# Replicape_A4.net
KiCad netlist of a schematic drawn in EAGLE
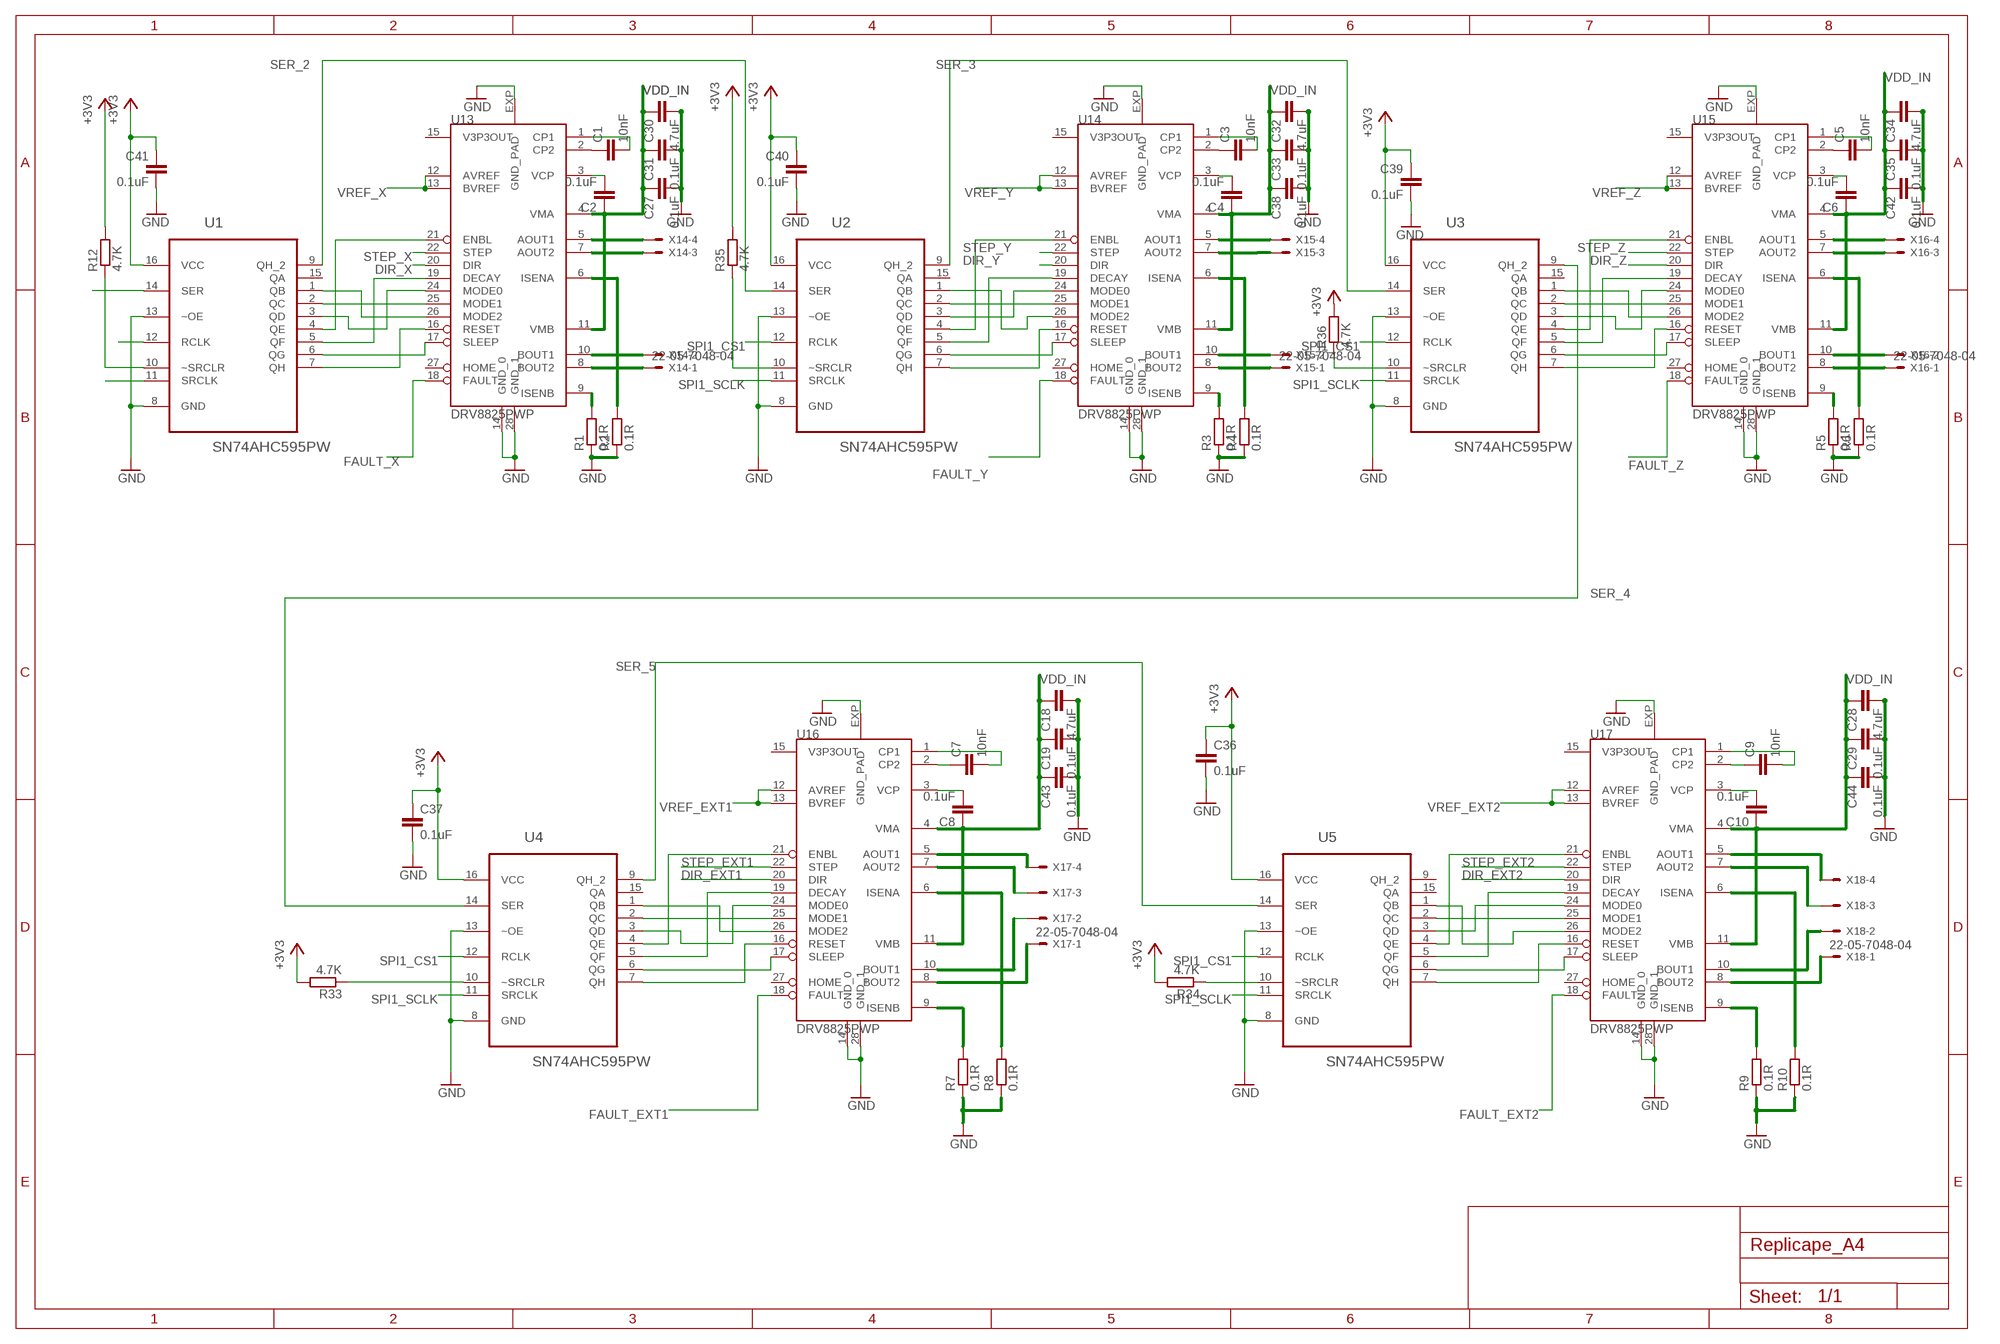
[diagram p0: schematic, sheet 1, part 1 of 3]
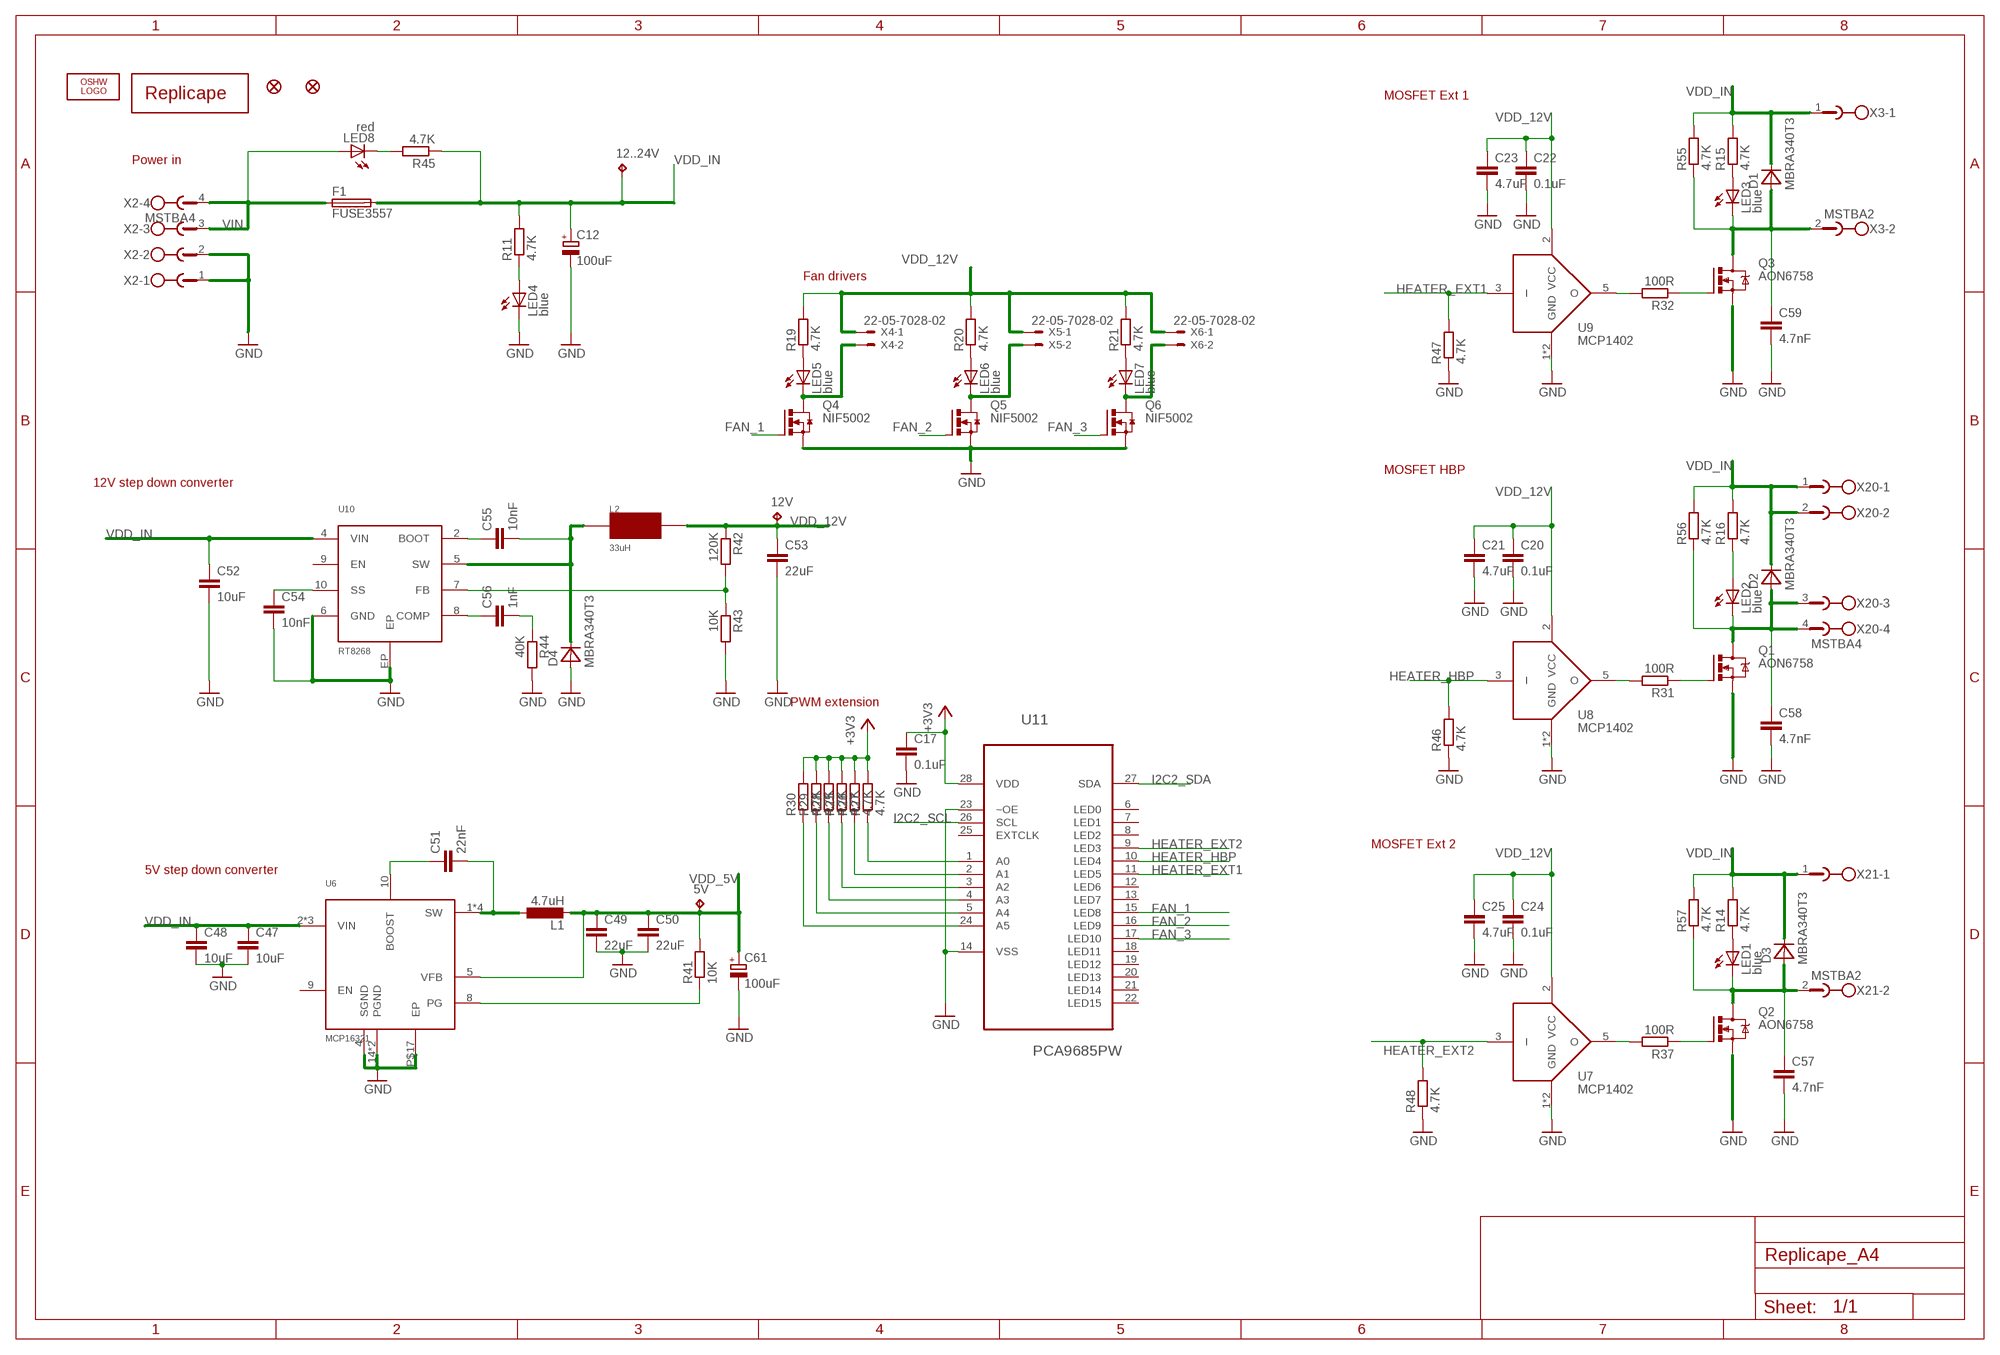
[diagram p1: schematic, sheet 1, part 2 of 3]
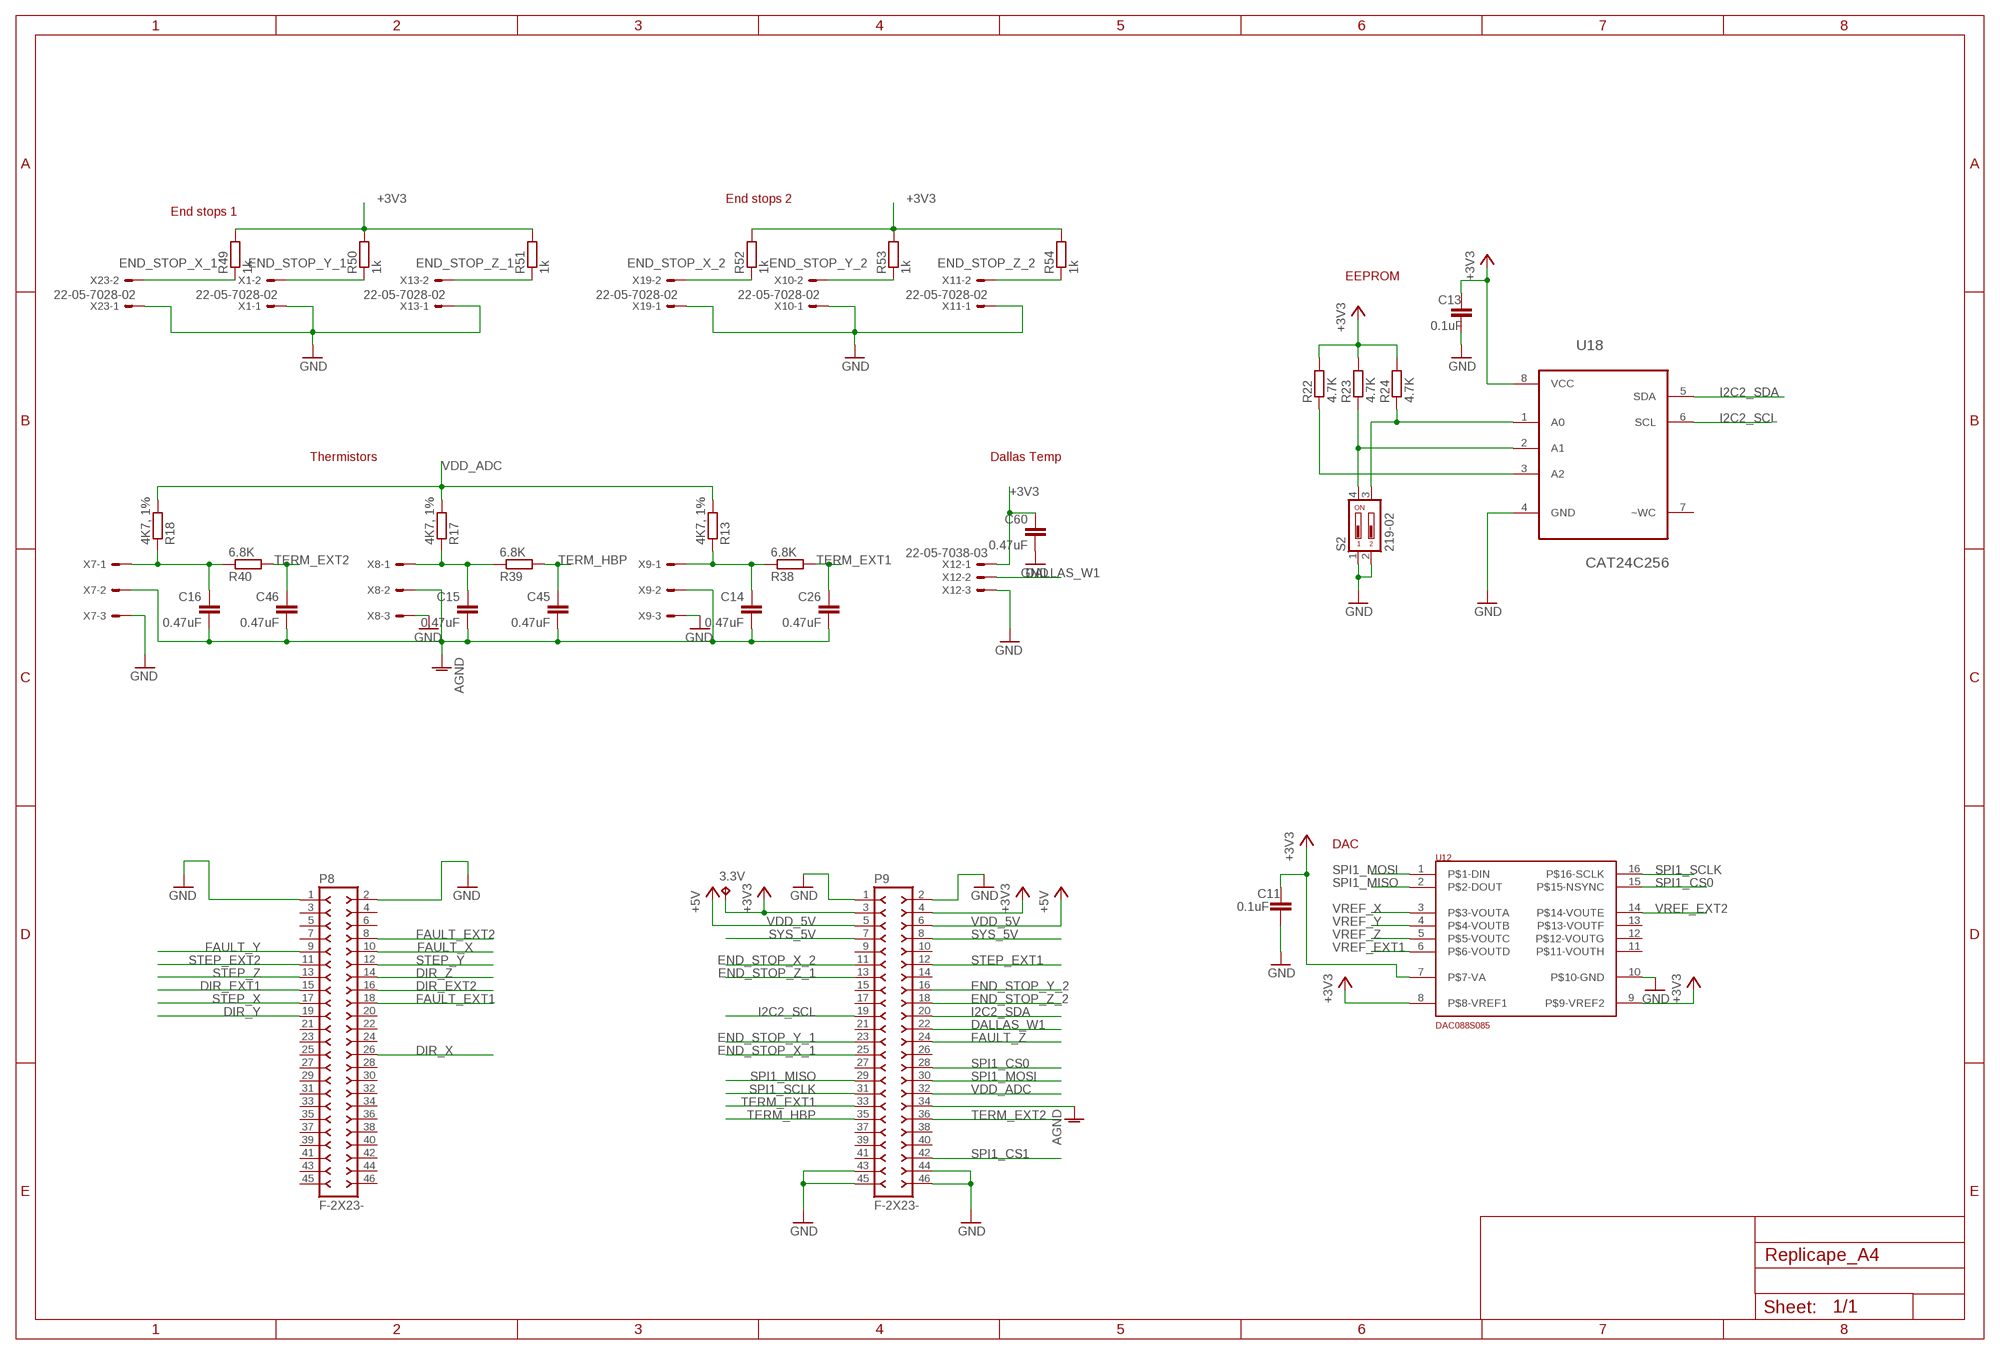
[diagram p2: schematic, sheet 1, part 3 of 3]

(export (version "E")
  (design (tool "Eeschema 10.0.6"))
  (components
    (comp (ref "3.3V")
      (value "TPB1,27")
      (footprint "eagle-import:B1,27")
      (libsource (lib "eagle-import") (part "TPB1,27"))
    )
    (comp (ref "5V")
      (value "TPB1,27")
      (footprint "eagle-import:B1,27")
      (libsource (lib "eagle-import") (part "TPB1,27"))
    )
    (comp (ref "12..24V")
      (value "TPB1,27")
      (footprint "eagle-import:B1,27")
      (libsource (lib "eagle-import") (part "TPB1,27"))
    )
    (comp (ref "12V")
      (value "TPB1,27")
      (footprint "eagle-import:B1,27")
      (libsource (lib "eagle-import") (part "TPB1,27"))
    )
    (comp (ref "C1")
      (value "10nF")
      (footprint "eagle-import:C0402")
      (libsource (lib "eagle-import") (part "C-EUC0402"))
    )
    (comp (ref "C2")
      (value "0.1uF")
      (footprint "eagle-import:C0402")
      (libsource (lib "eagle-import") (part "C-EUC0402"))
    )
    (comp (ref "C3")
      (value "10nF")
      (footprint "eagle-import:C0402")
      (libsource (lib "eagle-import") (part "C-EUC0402"))
    )
    (comp (ref "C4")
      (value "0.1uF")
      (footprint "eagle-import:C0402")
      (libsource (lib "eagle-import") (part "C-EUC0402"))
    )
    (comp (ref "C5")
      (value "10nF")
      (footprint "eagle-import:C0402")
      (libsource (lib "eagle-import") (part "C-EUC0402"))
    )
    (comp (ref "C6")
      (value "0.1uF")
      (footprint "eagle-import:C0402")
      (libsource (lib "eagle-import") (part "C-EUC0402"))
    )
    (comp (ref "C7")
      (value "10nF")
      (footprint "eagle-import:C0402")
      (libsource (lib "eagle-import") (part "C-EUC0402"))
    )
    (comp (ref "C8")
      (value "0.1uF")
      (footprint "eagle-import:C0402")
      (libsource (lib "eagle-import") (part "C-EUC0402"))
    )
    (comp (ref "C9")
      (value "10nF")
      (footprint "eagle-import:C0402")
      (libsource (lib "eagle-import") (part "C-EUC0402"))
    )
    (comp (ref "C10")
      (value "0.1uF")
      (footprint "eagle-import:C0402")
      (libsource (lib "eagle-import") (part "C-EUC0402"))
    )
    (comp (ref "C11")
      (value "0.1uF")
      (footprint "eagle-import:C0402")
      (libsource (lib "eagle-import") (part "C-EUC0402"))
    )
    (comp (ref "C12")
      (value "100uF")
      (footprint "eagle-import:140CLH-0810")
      (libsource (lib "eagle-import") (part "CPOL-EU140CLH-0810"))
    )
    (comp (ref "C13")
      (value "0.1uF")
      (footprint "eagle-import:C0402")
      (libsource (lib "eagle-import") (part "C-EUC0402"))
    )
    (comp (ref "C14")
      (value "0.47uF")
      (footprint "eagle-import:C0402")
      (libsource (lib "eagle-import") (part "C-EUC0402"))
    )
    (comp (ref "C15")
      (value "0.47uF")
      (footprint "eagle-import:C0402")
      (libsource (lib "eagle-import") (part "C-EUC0402"))
    )
    (comp (ref "C16")
      (value "0.47uF")
      (footprint "eagle-import:C0402")
      (libsource (lib "eagle-import") (part "C-EUC0402"))
    )
    (comp (ref "C17")
      (value "0.1uF")
      (footprint "eagle-import:C0402")
      (libsource (lib "eagle-import") (part "C-EUC0402"))
    )
    (comp (ref "C18")
      (value "4.7uF")
      (footprint "eagle-import:C0603")
      (libsource (lib "eagle-import") (part "C-EUC0603"))
    )
    (comp (ref "C19")
      (value "0.1uF")
      (footprint "eagle-import:C0402")
      (libsource (lib "eagle-import") (part "C-EUC0402"))
    )
    (comp (ref "C20")
      (value "0.1uF")
      (footprint "eagle-import:C0402")
      (libsource (lib "eagle-import") (part "C-EUC0402"))
    )
    (comp (ref "C21")
      (value "4.7uF")
      (footprint "eagle-import:C0402")
      (libsource (lib "eagle-import") (part "C-EUC0402"))
    )
    (comp (ref "C22")
      (value "0.1uF")
      (footprint "eagle-import:C0402")
      (libsource (lib "eagle-import") (part "C-EUC0402"))
    )
    (comp (ref "C23")
      (value "4.7uF")
      (footprint "eagle-import:C0402")
      (libsource (lib "eagle-import") (part "C-EUC0402"))
    )
    (comp (ref "C24")
      (value "0.1uF")
      (footprint "eagle-import:C0402")
      (libsource (lib "eagle-import") (part "C-EUC0402"))
    )
    (comp (ref "C25")
      (value "4.7uF")
      (footprint "eagle-import:C0402")
      (libsource (lib "eagle-import") (part "C-EUC0402"))
    )
    (comp (ref "C26")
      (value "0.47uF")
      (footprint "eagle-import:C0402")
      (libsource (lib "eagle-import") (part "C-EUC0402"))
    )
    (comp (ref "C27")
      (value "0.1uF")
      (footprint "eagle-import:C0402")
      (libsource (lib "eagle-import") (part "C-EUC0402"))
    )
    (comp (ref "C28")
      (value "4.7uF")
      (footprint "eagle-import:C0603")
      (libsource (lib "eagle-import") (part "C-EUC0603"))
    )
    (comp (ref "C29")
      (value "0.1uF")
      (footprint "eagle-import:C0402")
      (libsource (lib "eagle-import") (part "C-EUC0402"))
    )
    (comp (ref "C30")
      (value "4.7uF")
      (footprint "eagle-import:C0603")
      (libsource (lib "eagle-import") (part "C-EUC0603"))
    )
    (comp (ref "C31")
      (value "0.1uF")
      (footprint "eagle-import:C0402")
      (libsource (lib "eagle-import") (part "C-EUC0402"))
    )
    (comp (ref "C32")
      (value "4.7uF")
      (footprint "eagle-import:C0603")
      (libsource (lib "eagle-import") (part "C-EUC0603"))
    )
    (comp (ref "C33")
      (value "0.1uF")
      (footprint "eagle-import:C0402")
      (libsource (lib "eagle-import") (part "C-EUC0402"))
    )
    (comp (ref "C34")
      (value "4.7uF")
      (footprint "eagle-import:C0603")
      (libsource (lib "eagle-import") (part "C-EUC0603"))
    )
    (comp (ref "C35")
      (value "0.1uF")
      (footprint "eagle-import:C0402")
      (libsource (lib "eagle-import") (part "C-EUC0402"))
    )
    (comp (ref "C36")
      (value "0.1uF")
      (footprint "eagle-import:C0402")
      (libsource (lib "eagle-import") (part "C-EUC0402"))
    )
    (comp (ref "C37")
      (value "0.1uF")
      (footprint "eagle-import:C0402")
      (libsource (lib "eagle-import") (part "C-EUC0402"))
    )
    (comp (ref "C38")
      (value "0.1uF")
      (footprint "eagle-import:C0402")
      (libsource (lib "eagle-import") (part "C-EUC0402"))
    )
    (comp (ref "C39")
      (value "0.1uF")
      (footprint "eagle-import:C0402")
      (libsource (lib "eagle-import") (part "C-EUC0402"))
    )
    (comp (ref "C40")
      (value "0.1uF")
      (footprint "eagle-import:C0402")
      (libsource (lib "eagle-import") (part "C-EUC0402"))
    )
    (comp (ref "C41")
      (value "0.1uF")
      (footprint "eagle-import:C0402")
      (libsource (lib "eagle-import") (part "C-EUC0402"))
    )
    (comp (ref "C42")
      (value "0.1uF")
      (footprint "eagle-import:C0402")
      (libsource (lib "eagle-import") (part "C-EUC0402"))
    )
    (comp (ref "C43")
      (value "0.1uF")
      (footprint "eagle-import:C0402")
      (libsource (lib "eagle-import") (part "C-EUC0402"))
    )
    (comp (ref "C44")
      (value "0.1uF")
      (footprint "eagle-import:C0402")
      (libsource (lib "eagle-import") (part "C-EUC0402"))
    )
    (comp (ref "C45")
      (value "0.47uF")
      (footprint "eagle-import:C0402")
      (libsource (lib "eagle-import") (part "C-EUC0402"))
    )
    (comp (ref "C46")
      (value "0.47uF")
      (footprint "eagle-import:C0402")
      (libsource (lib "eagle-import") (part "C-EUC0402"))
    )
    (comp (ref "C47")
      (value "10uF")
      (footprint "eagle-import:C1206")
      (libsource (lib "eagle-import") (part "C-EUC1206"))
    )
    (comp (ref "C48")
      (value "10uF")
      (footprint "eagle-import:C1206")
      (libsource (lib "eagle-import") (part "C-EUC1206"))
    )
    (comp (ref "C49")
      (value "22uF")
      (footprint "eagle-import:C0805")
      (libsource (lib "eagle-import") (part "C-EUC0805"))
    )
    (comp (ref "C50")
      (value "22uF")
      (footprint "eagle-import:C0805")
      (libsource (lib "eagle-import") (part "C-EUC0805"))
    )
    (comp (ref "C51")
      (value "22nF")
      (footprint "eagle-import:C0402")
      (libsource (lib "eagle-import") (part "C-EUC0402"))
    )
    (comp (ref "C52")
      (value "10uF")
      (footprint "eagle-import:C1206")
      (libsource (lib "eagle-import") (part "C-EUC1206"))
    )
    (comp (ref "C53")
      (value "22uF")
      (footprint "eagle-import:C0805")
      (libsource (lib "eagle-import") (part "C-EUC0805"))
    )
    (comp (ref "C54")
      (value "10nF")
      (footprint "eagle-import:C0402")
      (libsource (lib "eagle-import") (part "C-EUC0402"))
    )
    (comp (ref "C55")
      (value "10nF")
      (footprint "eagle-import:C0402")
      (libsource (lib "eagle-import") (part "C-EUC0402"))
    )
    (comp (ref "C56")
      (value "1nF")
      (footprint "eagle-import:C0402")
      (libsource (lib "eagle-import") (part "C-EUC0402"))
    )
    (comp (ref "C57")
      (value "4.7nF")
      (footprint "eagle-import:C0402")
      (libsource (lib "eagle-import") (part "C-EUC0402"))
    )
    (comp (ref "C58")
      (value "4.7nF")
      (footprint "eagle-import:C0402")
      (libsource (lib "eagle-import") (part "C-EUC0402"))
    )
    (comp (ref "C59")
      (value "4.7nF")
      (footprint "eagle-import:C0402")
      (libsource (lib "eagle-import") (part "C-EUC0402"))
    )
    (comp (ref "C60")
      (value "0.47uF")
      (footprint "eagle-import:C0402")
      (libsource (lib "eagle-import") (part "C-EUC0402"))
    )
    (comp (ref "C61")
      (value "100uF")
      (footprint "eagle-import:140CLH-0810")
      (libsource (lib "eagle-import") (part "CPOL-EU140CLH-0810"))
    )
    (comp (ref "D1")
      (value "MBRA340T3")
      (footprint "eagle-import:SMA")
      (libsource (lib "eagle-import") (part "MBRA340T3"))
    )
    (comp (ref "D2")
      (value "MBRA340T3")
      (footprint "eagle-import:SMA")
      (libsource (lib "eagle-import") (part "MBRA340T3"))
    )
    (comp (ref "D3")
      (value "MBRA340T3")
      (footprint "eagle-import:SMA")
      (libsource (lib "eagle-import") (part "MBRA340T3"))
    )
    (comp (ref "D4")
      (value "MBRA340T3")
      (footprint "eagle-import:SMA")
      (libsource (lib "eagle-import") (part "MBRA340T3"))
    )
    (comp (ref "F1")
      (value "FUSE3557")
      (footprint "eagle-import:3557")
      (libsource (lib "eagle-import") (part "FUSE3557"))
    )
    (comp (ref "JP1")
      (value "FIDUCIAL1X2.5")
      (footprint "eagle-import:FIDUCIAL-1X2.5")
      (libsource (lib "eagle-import") (part "FIDUCIAL1X2.5"))
    )
    (comp (ref "JP2")
      (value "FIDUCIAL1X2.5")
      (footprint "eagle-import:FIDUCIAL-1X2.5")
      (libsource (lib "eagle-import") (part "FIDUCIAL1X2.5"))
    )
    (comp (ref "L1")
      (value "4.7uH")
      (footprint "eagle-import:VLC5020")
      (libsource (lib "eagle-import") (part "L-EUVLC"))
    )
    (comp (ref "L2")
      (value "33uH")
      (footprint "eagle-import:NR8040T330")
      (libsource (lib "eagle-import") (part "RT8040T330"))
    )
    (comp (ref "LED1")
      (value "blue")
      (footprint "eagle-import:CHIP-LED0603")
      (libsource (lib "eagle-import") (part "LEDCHIP-LED0603"))
    )
    (comp (ref "LED2")
      (value "blue")
      (footprint "eagle-import:CHIP-LED0603")
      (libsource (lib "eagle-import") (part "LEDCHIP-LED0603"))
    )
    (comp (ref "LED3")
      (value "blue")
      (footprint "eagle-import:CHIP-LED0603")
      (libsource (lib "eagle-import") (part "LEDCHIP-LED0603"))
    )
    (comp (ref "LED4")
      (value "blue")
      (footprint "eagle-import:CHIP-LED0603")
      (libsource (lib "eagle-import") (part "LEDCHIP-LED0603"))
    )
    (comp (ref "LED5")
      (value "blue")
      (footprint "eagle-import:CHIP-LED0603")
      (libsource (lib "eagle-import") (part "LEDCHIP-LED0603"))
    )
    (comp (ref "LED6")
      (value "blue")
      (footprint "eagle-import:CHIP-LED0603")
      (libsource (lib "eagle-import") (part "LEDCHIP-LED0603"))
    )
    (comp (ref "LED7")
      (value "blue")
      (footprint "eagle-import:CHIP-LED0603")
      (libsource (lib "eagle-import") (part "LEDCHIP-LED0603"))
    )
    (comp (ref "LED8")
      (value "red")
      (footprint "eagle-import:CHIP-LED0603")
      (libsource (lib "eagle-import") (part "LEDCHIP-LED0603"))
    )
    (comp (ref "LOGO1")
      (value "OSHW_LOGO_FILLX0200-NT")
      (footprint "eagle-import:OSHW_FILLX200_NOTEXT")
      (libsource (lib "eagle-import") (part "OSHW_LOGO_FILLX0200-NT"))
    )
    (comp (ref "P8")
      (value "F-2X23-")
      (footprint "eagle-import:DIL-100-2X23")
      (libsource (lib "eagle-import") (part "F-2X23-"))
    )
    (comp (ref "P9")
      (value "F-2X23-")
      (footprint "eagle-import:DIL-100-2X23")
      (libsource (lib "eagle-import") (part "F-2X23-"))
    )
    (comp (ref "Q1")
      (value "AON6758")
      (footprint "eagle-import:8-DFN-EP-(5X6)")
      (libsource (lib "eagle-import") (part "AON6758"))
    )
    (comp (ref "Q2")
      (value "AON6758")
      (footprint "eagle-import:8-DFN-EP-(5X6)")
      (libsource (lib "eagle-import") (part "AON6758"))
    )
    (comp (ref "Q3")
      (value "AON6758")
      (footprint "eagle-import:8-DFN-EP-(5X6)")
      (libsource (lib "eagle-import") (part "AON6758"))
    )
    (comp (ref "Q4")
      (value "NIF5002")
      (footprint "eagle-import:SOT223")
      (libsource (lib "eagle-import") (part "N-HEXFET-2D_?-SOT232"))
    )
    (comp (ref "Q5")
      (value "NIF5002")
      (footprint "eagle-import:SOT223")
      (libsource (lib "eagle-import") (part "N-HEXFET-2D_?-SOT232"))
    )
    (comp (ref "Q6")
      (value "NIF5002")
      (footprint "eagle-import:SOT223")
      (libsource (lib "eagle-import") (part "N-HEXFET-2D_?-SOT232"))
    )
    (comp (ref "R1")
      (value "0.1R")
      (footprint "eagle-import:R0805")
      (libsource (lib "eagle-import") (part "R-EU_R0805"))
    )
    (comp (ref "R2")
      (value "0.1R")
      (footprint "eagle-import:R0805")
      (libsource (lib "eagle-import") (part "R-EU_R0805"))
    )
    (comp (ref "R3")
      (value "0.1R")
      (footprint "eagle-import:R0805")
      (libsource (lib "eagle-import") (part "R-EU_R0805"))
    )
    (comp (ref "R4")
      (value "0.1R")
      (footprint "eagle-import:R0805")
      (libsource (lib "eagle-import") (part "R-EU_R0805"))
    )
    (comp (ref "R5")
      (value "0.1R")
      (footprint "eagle-import:R0805")
      (libsource (lib "eagle-import") (part "R-EU_R0805"))
    )
    (comp (ref "R6")
      (value "0.1R")
      (footprint "eagle-import:R0805")
      (libsource (lib "eagle-import") (part "R-EU_R0805"))
    )
    (comp (ref "R7")
      (value "0.1R")
      (footprint "eagle-import:R0805")
      (libsource (lib "eagle-import") (part "R-EU_R0805"))
    )
    (comp (ref "R8")
      (value "0.1R")
      (footprint "eagle-import:R0805")
      (libsource (lib "eagle-import") (part "R-EU_R0805"))
    )
    (comp (ref "R9")
      (value "0.1R")
      (footprint "eagle-import:R0805")
      (libsource (lib "eagle-import") (part "R-EU_R0805"))
    )
    (comp (ref "R10")
      (value "0.1R")
      (footprint "eagle-import:R0805")
      (libsource (lib "eagle-import") (part "R-EU_R0805"))
    )
    (comp (ref "R11")
      (value "4.7K")
      (footprint "eagle-import:R0402")
      (libsource (lib "eagle-import") (part "R-EU_R0402"))
    )
    (comp (ref "R12")
      (value "4.7K")
      (footprint "eagle-import:R0402")
      (libsource (lib "eagle-import") (part "R-EU_R0402"))
    )
    (comp (ref "R13")
      (value "4K7, 1%")
      (footprint "eagle-import:R0402")
      (libsource (lib "eagle-import") (part "R-EU_R0402"))
    )
    (comp (ref "R14")
      (value "4.7K")
      (footprint "eagle-import:R0402")
      (libsource (lib "eagle-import") (part "R-EU_R0402"))
    )
    (comp (ref "R15")
      (value "4.7K")
      (footprint "eagle-import:R0402")
      (libsource (lib "eagle-import") (part "R-EU_R0402"))
    )
    (comp (ref "R16")
      (value "4.7K")
      (footprint "eagle-import:R0402")
      (libsource (lib "eagle-import") (part "R-EU_R0402"))
    )
    (comp (ref "R17")
      (value "4K7, 1%")
      (footprint "eagle-import:R0402")
      (libsource (lib "eagle-import") (part "R-EU_R0402"))
    )
    (comp (ref "R18")
      (value "4K7, 1%")
      (footprint "eagle-import:R0402")
      (libsource (lib "eagle-import") (part "R-EU_R0402"))
    )
    (comp (ref "R19")
      (value "4.7K")
      (footprint "eagle-import:R0402")
      (libsource (lib "eagle-import") (part "R-EU_R0402"))
    )
    (comp (ref "R20")
      (value "4.7K")
      (footprint "eagle-import:R0402")
      (libsource (lib "eagle-import") (part "R-EU_R0402"))
    )
    (comp (ref "R21")
      (value "4.7K")
      (footprint "eagle-import:R0402")
      (libsource (lib "eagle-import") (part "R-EU_R0402"))
    )
    (comp (ref "R22")
      (value "4.7K")
      (footprint "eagle-import:R0402")
      (libsource (lib "eagle-import") (part "R-EU_R0402"))
    )
    (comp (ref "R23")
      (value "4.7K")
      (footprint "eagle-import:R0402")
      (libsource (lib "eagle-import") (part "R-EU_R0402"))
    )
    (comp (ref "R24")
      (value "4.7K")
      (footprint "eagle-import:R0402")
      (libsource (lib "eagle-import") (part "R-EU_R0402"))
    )
    (comp (ref "R25")
      (value "4.7K")
      (footprint "eagle-import:R0402")
      (libsource (lib "eagle-import") (part "R-EU_R0402"))
    )
    (comp (ref "R26")
      (value "4.7K")
      (footprint "eagle-import:R0402")
      (libsource (lib "eagle-import") (part "R-EU_R0402"))
    )
    (comp (ref "R27")
      (value "4.7K")
      (footprint "eagle-import:R0402")
      (libsource (lib "eagle-import") (part "R-EU_R0402"))
    )
    (comp (ref "R28")
      (value "4.7K")
      (footprint "eagle-import:R0402")
      (libsource (lib "eagle-import") (part "R-EU_R0402"))
    )
    (comp (ref "R29")
      (value "4.7K")
      (footprint "eagle-import:R0402")
      (libsource (lib "eagle-import") (part "R-EU_R0402"))
    )
    (comp (ref "R30")
      (value "4.7K")
      (footprint "eagle-import:R0402")
      (libsource (lib "eagle-import") (part "R-EU_R0402"))
    )
    (comp (ref "R31")
      (value "100R")
      (footprint "eagle-import:R0402")
      (libsource (lib "eagle-import") (part "R-EU_R0402"))
    )
    (comp (ref "R32")
      (value "100R")
      (footprint "eagle-import:R0402")
      (libsource (lib "eagle-import") (part "R-EU_R0402"))
    )
    (comp (ref "R33")
      (value "4.7K")
      (footprint "eagle-import:R0402")
      (libsource (lib "eagle-import") (part "R-EU_R0402"))
    )
    (comp (ref "R34")
      (value "4.7K")
      (footprint "eagle-import:R0402")
      (libsource (lib "eagle-import") (part "R-EU_R0402"))
    )
    (comp (ref "R35")
      (value "4.7K")
      (footprint "eagle-import:R0402")
      (libsource (lib "eagle-import") (part "R-EU_R0402"))
    )
    (comp (ref "R36")
      (value "4.7K")
      (footprint "eagle-import:R0402")
      (libsource (lib "eagle-import") (part "R-EU_R0402"))
    )
    (comp (ref "R37")
      (value "100R")
      (footprint "eagle-import:R0402")
      (libsource (lib "eagle-import") (part "R-EU_R0402"))
    )
    (comp (ref "R38")
      (value "6.8K")
      (footprint "eagle-import:R0402")
      (libsource (lib "eagle-import") (part "R-EU_R0402"))
    )
    (comp (ref "R39")
      (value "6.8K")
      (footprint "eagle-import:R0402")
      (libsource (lib "eagle-import") (part "R-EU_R0402"))
    )
    (comp (ref "R40")
      (value "6.8K")
      (footprint "eagle-import:R0402")
      (libsource (lib "eagle-import") (part "R-EU_R0402"))
    )
    (comp (ref "R41")
      (value "10K")
      (footprint "eagle-import:R0402")
      (libsource (lib "eagle-import") (part "R-EU_R0402"))
    )
    (comp (ref "R42")
      (value "120K")
      (footprint "eagle-import:R0402")
      (libsource (lib "eagle-import") (part "R-EU_R0402"))
    )
    (comp (ref "R43")
      (value "10K")
      (footprint "eagle-import:R0402")
      (libsource (lib "eagle-import") (part "R-EU_R0402"))
    )
    (comp (ref "R44")
      (value "40K")
      (footprint "eagle-import:R0402")
      (libsource (lib "eagle-import") (part "R-EU_R0402"))
    )
    (comp (ref "R45")
      (value "4.7K")
      (footprint "eagle-import:R0402")
      (libsource (lib "eagle-import") (part "R-EU_R0402"))
    )
    (comp (ref "R46")
      (value "4.7K")
      (footprint "eagle-import:R0402")
      (libsource (lib "eagle-import") (part "R-EU_R0402"))
    )
    (comp (ref "R47")
      (value "4.7K")
      (footprint "eagle-import:R0402")
      (libsource (lib "eagle-import") (part "R-EU_R0402"))
    )
    (comp (ref "R48")
      (value "4.7K")
      (footprint "eagle-import:R0402")
      (libsource (lib "eagle-import") (part "R-EU_R0402"))
    )
    (comp (ref "R49")
      (value "1k")
      (footprint "eagle-import:R0402")
      (libsource (lib "eagle-import") (part "R-EUR0402"))
    )
    (comp (ref "R50")
      (value "1k")
      (footprint "eagle-import:R0402")
      (libsource (lib "eagle-import") (part "R-EUR0402"))
    )
    (comp (ref "R51")
      (value "1k")
      (footprint "eagle-import:R0402")
      (libsource (lib "eagle-import") (part "R-EUR0402"))
    )
    (comp (ref "R52")
      (value "1k")
      (footprint "eagle-import:R0402")
      (libsource (lib "eagle-import") (part "R-EUR0402"))
    )
    (comp (ref "R53")
      (value "1k")
      (footprint "eagle-import:R0402")
      (libsource (lib "eagle-import") (part "R-EUR0402"))
    )
    (comp (ref "R54")
      (value "1k")
      (footprint "eagle-import:R0402")
      (libsource (lib "eagle-import") (part "R-EUR0402"))
    )
    (comp (ref "R55")
      (value "4.7K")
      (footprint "eagle-import:R0402")
      (libsource (lib "eagle-import") (part "R-EU_R0402"))
    )
    (comp (ref "R56")
      (value "4.7K")
      (footprint "eagle-import:R0402")
      (libsource (lib "eagle-import") (part "R-EU_R0402"))
    )
    (comp (ref "R57")
      (value "4.7K")
      (footprint "eagle-import:R0402")
      (libsource (lib "eagle-import") (part "R-EU_R0402"))
    )
    (comp (ref "S2")
      (value "219-02")
      (footprint "eagle-import:CTS-219-02")
      (libsource (lib "eagle-import") (part "219-02"))
    )
    (comp (ref "U$2")
      (value "REPLICAPE-LOGO")
      (footprint "eagle-import:REPLICAPE-LOGO")
      (libsource (lib "eagle-import") (part "REPLICAPE-LOGO"))
    )
    (comp (ref "U1")
      (value "SN74AHC595PW")
      (footprint "eagle-import:SOP65P640X120-16N")
      (libsource (lib "eagle-import") (part "SN74AHC595PW"))
    )
    (comp (ref "U2")
      (value "SN74AHC595PW")
      (footprint "eagle-import:SOP65P640X120-16N")
      (libsource (lib "eagle-import") (part "SN74AHC595PW"))
    )
    (comp (ref "U3")
      (value "SN74AHC595PW")
      (footprint "eagle-import:SOP65P640X120-16N")
      (libsource (lib "eagle-import") (part "SN74AHC595PW"))
    )
    (comp (ref "U4")
      (value "SN74AHC595PW")
      (footprint "eagle-import:SOP65P640X120-16N")
      (libsource (lib "eagle-import") (part "SN74AHC595PW"))
    )
    (comp (ref "U5")
      (value "SN74AHC595PW")
      (footprint "eagle-import:SOP65P640X120-16N")
      (libsource (lib "eagle-import") (part "SN74AHC595PW"))
    )
    (comp (ref "U6")
      (value "MCP16321")
      (footprint "eagle-import:QFN-16")
      (libsource (lib "eagle-import") (part "MCP16321"))
    )
    (comp (ref "U7")
      (value "MCP1402")
      (footprint "eagle-import:SOT23-5L")
      (libsource (lib "eagle-import") (part "MCP1402"))
    )
    (comp (ref "U8")
      (value "MCP1402")
      (footprint "eagle-import:SOT23-5L")
      (libsource (lib "eagle-import") (part "MCP1402"))
    )
    (comp (ref "U9")
      (value "MCP1402")
      (footprint "eagle-import:SOT23-5L")
      (libsource (lib "eagle-import") (part "MCP1402"))
    )
    (comp (ref "U10")
      (value "RT8268")
      (footprint "eagle-import:MSOP10")
      (libsource (lib "eagle-import") (part "RT8268"))
    )
    (comp (ref "U11")
      (value "PCA9685PW")
      (footprint "eagle-import:SOP65P640X110-28N")
      (libsource (lib "eagle-import") (part "PCA9685PW"))
    )
    (comp (ref "U12")
      (value "DAC088S085")
      (footprint "eagle-import:TSSOP-16")
      (libsource (lib "eagle-import") (part "DAC088S085"))
    )
    (comp (ref "U13")
      (value "DRV8825PWP")
      (footprint "eagle-import:TSSOP-28")
      (libsource (lib "eagle-import") (part "DRV8825PWP"))
    )
    (comp (ref "U14")
      (value "DRV8825PWP")
      (footprint "eagle-import:TSSOP-28")
      (libsource (lib "eagle-import") (part "DRV8825PWP"))
    )
    (comp (ref "U15")
      (value "DRV8825PWP")
      (footprint "eagle-import:TSSOP-28")
      (libsource (lib "eagle-import") (part "DRV8825PWP"))
    )
    (comp (ref "U16")
      (value "DRV8825PWP")
      (footprint "eagle-import:TSSOP-28")
      (libsource (lib "eagle-import") (part "DRV8825PWP"))
    )
    (comp (ref "U17")
      (value "DRV8825PWP")
      (footprint "eagle-import:TSSOP-28")
      (libsource (lib "eagle-import") (part "DRV8825PWP"))
    )
    (comp (ref "U18")
      (value "CAT24C256")
      (footprint "eagle-import:SOIC127P600X175-8N")
      (libsource (lib "eagle-import") (part "CAT24C256"))
    )
    (comp (ref "X1")
      (value "22-05-7028-02")
      (footprint "eagle-import:7395-02")
      (libsource (lib "eagle-import") (part "22-?-0205-7028"))
    )
    (comp (ref "X2")
      (value "MSTBA4")
      (footprint "eagle-import:MSTBA4")
      (libsource (lib "eagle-import") (part "MSTBA4"))
    )
    (comp (ref "X3")
      (value "MSTBA2")
      (footprint "eagle-import:MSTBA2")
      (libsource (lib "eagle-import") (part "MSTBA2"))
    )
    (comp (ref "X4")
      (value "22-05-7028-02")
      (footprint "eagle-import:7395-02")
      (libsource (lib "eagle-import") (part "22-?-0205-7028"))
    )
    (comp (ref "X5")
      (value "22-05-7028-02")
      (footprint "eagle-import:7395-02")
      (libsource (lib "eagle-import") (part "22-?-0205-7028"))
    )
    (comp (ref "X6")
      (value "22-05-7028-02")
      (footprint "eagle-import:7395-02")
      (libsource (lib "eagle-import") (part "22-?-0205-7028"))
    )
    (comp (ref "X7")
      (value "22-05-7038-03")
      (footprint "eagle-import:7395-03")
      (libsource (lib "eagle-import") (part "22-?-0305-7038"))
    )
    (comp (ref "X8")
      (value "22-05-7038-03")
      (footprint "eagle-import:7395-03")
      (libsource (lib "eagle-import") (part "22-?-0305-7038"))
    )
    (comp (ref "X9")
      (value "22-05-7038-03")
      (footprint "eagle-import:7395-03")
      (libsource (lib "eagle-import") (part "22-?-0305-7038"))
    )
    (comp (ref "X10")
      (value "22-05-7028-02")
      (footprint "eagle-import:7395-02")
      (libsource (lib "eagle-import") (part "22-?-0205-7028"))
    )
    (comp (ref "X11")
      (value "22-05-7028-02")
      (footprint "eagle-import:7395-02")
      (libsource (lib "eagle-import") (part "22-?-0205-7028"))
    )
    (comp (ref "X12")
      (value "22-05-7038-03")
      (footprint "eagle-import:7395-03")
      (libsource (lib "eagle-import") (part "22-?-0305-7038"))
    )
    (comp (ref "X13")
      (value "22-05-7028-02")
      (footprint "eagle-import:7395-02")
      (libsource (lib "eagle-import") (part "22-?-0205-7028"))
    )
    (comp (ref "X14")
      (value "22-05-7048-04")
      (footprint "eagle-import:7395-04")
      (libsource (lib "eagle-import") (part "22-?-0405-7048"))
    )
    (comp (ref "X15")
      (value "22-05-7048-04")
      (footprint "eagle-import:7395-04")
      (libsource (lib "eagle-import") (part "22-?-0405-7048"))
    )
    (comp (ref "X16")
      (value "22-05-7048-04")
      (footprint "eagle-import:7395-04")
      (libsource (lib "eagle-import") (part "22-?-0405-7048"))
    )
    (comp (ref "X17")
      (value "22-05-7048-04")
      (footprint "eagle-import:7395-04")
      (libsource (lib "eagle-import") (part "22-?-0405-7048"))
    )
    (comp (ref "X18")
      (value "22-05-7048-04")
      (footprint "eagle-import:7395-04")
      (libsource (lib "eagle-import") (part "22-?-0405-7048"))
    )
    (comp (ref "X19")
      (value "22-05-7028-02")
      (footprint "eagle-import:7395-02")
      (libsource (lib "eagle-import") (part "22-?-0205-7028"))
    )
    (comp (ref "X20")
      (value "MSTBA4")
      (footprint "eagle-import:MSTBA4")
      (libsource (lib "eagle-import") (part "MSTBA4"))
    )
    (comp (ref "X21")
      (value "MSTBA2")
      (footprint "eagle-import:MSTBA2")
      (libsource (lib "eagle-import") (part "MSTBA2"))
    )
    (comp (ref "X23")
      (value "22-05-7028-02")
      (footprint "eagle-import:7395-02")
      (libsource (lib "eagle-import") (part "22-?-0205-7028"))
    )
  )
  (nets
    (net (code "1") (name "+3V3") (class "Default")
      (node (ref "3.3V") (pin "TP") (pinfunction "TP_TP") (pintype "input"))
      (node (ref "C11") (pin "1") (pinfunction "1_1") (pintype "passive"))
      (node (ref "C13") (pin "1") (pinfunction "1_1") (pintype "passive"))
      (node (ref "C17") (pin "1") (pinfunction "1_1") (pintype "passive"))
      (node (ref "C36") (pin "1") (pinfunction "1_1") (pintype "passive"))
      (node (ref "C37") (pin "1") (pinfunction "1_1") (pintype "passive"))
      (node (ref "C39") (pin "1") (pinfunction "1_1") (pintype "passive"))
      (node (ref "C40") (pin "1") (pinfunction "1_1") (pintype "passive"))
      (node (ref "C41") (pin "1") (pinfunction "1_1") (pintype "passive"))
      (node (ref "C60") (pin "1") (pinfunction "1_1") (pintype "passive"))
      (node (ref "P9") (pin "3") (pinfunction "3_3") (pintype "passive"))
      (node (ref "P9") (pin "4") (pinfunction "4_4") (pintype "passive"))
      (node (ref "R12") (pin "2") (pinfunction "2_2") (pintype "passive"))
      (node (ref "R22") (pin "2") (pinfunction "2_2") (pintype "passive"))
      (node (ref "R23") (pin "2") (pinfunction "2_2") (pintype "passive"))
      (node (ref "R24") (pin "2") (pinfunction "2_2") (pintype "passive"))
      (node (ref "R25") (pin "2") (pinfunction "2_2") (pintype "passive"))
      (node (ref "R26") (pin "2") (pinfunction "2_2") (pintype "passive"))
      (node (ref "R27") (pin "2") (pinfunction "2_2") (pintype "passive"))
      (node (ref "R28") (pin "2") (pinfunction "2_2") (pintype "passive"))
      (node (ref "R29") (pin "2") (pinfunction "2_2") (pintype "passive"))
      (node (ref "R30") (pin "2") (pinfunction "2_2") (pintype "passive"))
      (node (ref "R33") (pin "2") (pinfunction "2_2") (pintype "passive"))
      (node (ref "R34") (pin "2") (pinfunction "2_2") (pintype "passive"))
      (node (ref "R35") (pin "2") (pinfunction "2_2") (pintype "passive"))
      (node (ref "R36") (pin "2") (pinfunction "2_2") (pintype "passive"))
      (node (ref "R49") (pin "2") (pinfunction "2_2") (pintype "passive"))
      (node (ref "R50") (pin "2") (pinfunction "2_2") (pintype "passive"))
      (node (ref "R51") (pin "2") (pinfunction "2_2") (pintype "passive"))
      (node (ref "R52") (pin "2") (pinfunction "2_2") (pintype "passive"))
      (node (ref "R53") (pin "2") (pinfunction "2_2") (pintype "passive"))
      (node (ref "R54") (pin "2") (pinfunction "2_2") (pintype "passive"))
      (node (ref "U1") (pin "16") (pinfunction "VCC_16") (pintype "power_in"))
      (node (ref "U11") (pin "28") (pinfunction "VDD_28") (pintype "power_in"))
      (node (ref "U12") (pin "7") (pinfunction "P$7-VA_7") (pintype "bidirectional"))
      (node (ref "U12") (pin "8") (pinfunction "P$8-VREF1_8") (pintype "bidirectional"))
      (node (ref "U12") (pin "9") (pinfunction "P$9-VREF2_9") (pintype "bidirectional"))
      (node (ref "U18") (pin "8") (pinfunction "VCC_8") (pintype "power_in"))
      (node (ref "U2") (pin "16") (pinfunction "VCC_16") (pintype "power_in"))
      (node (ref "U3") (pin "16") (pinfunction "VCC_16") (pintype "power_in"))
      (node (ref "U4") (pin "16") (pinfunction "VCC_16") (pintype "power_in"))
      (node (ref "U5") (pin "16") (pinfunction "VCC_16") (pintype "power_in"))
      (node (ref "X12") (pin "1") (pinfunction "S_1") (pintype "passive"))
    )
    (net (code "2") (name "+5V") (class "Default")
      (node (ref "5V") (pin "TP") (pinfunction "TP_TP") (pintype "input"))
      (node (ref "C49") (pin "1") (pinfunction "1_1") (pintype "passive"))
      (node (ref "C50") (pin "1") (pinfunction "1_1") (pintype "passive"))
      (node (ref "C61") (pin "+") (pinfunction "+_+") (pintype "passive"))
      (node (ref "L1") (pin "2") (pinfunction "2_2") (pintype "passive"))
      (node (ref "P9") (pin "5") (pinfunction "5_5") (pintype "passive"))
      (node (ref "P9") (pin "6") (pinfunction "6_6") (pintype "passive"))
      (node (ref "R41") (pin "2") (pinfunction "2_2") (pintype "passive"))
      (node (ref "U6") (pin "5") (pinfunction "VFB_5") (pintype "input"))
    )
    (net (code "3") (name "/DALLAS_W1") (class "Default")
      (node (ref "P9") (pin "22") (pinfunction "22_22") (pintype "passive"))
      (node (ref "X12") (pin "2") (pinfunction "S_2") (pintype "passive"))
    )
    (net (code "4") (name "/DIR_EXT1") (class "Default")
      (node (ref "P8") (pin "15") (pinfunction "15_15") (pintype "passive"))
      (node (ref "U16") (pin "20") (pinfunction "DIR_20") (pintype "input"))
    )
    (net (code "5") (name "/DIR_EXT2") (class "Default")
      (node (ref "P8") (pin "16") (pinfunction "16_16") (pintype "passive"))
      (node (ref "U17") (pin "20") (pinfunction "DIR_20") (pintype "input"))
    )
    (net (code "6") (name "/DIR_X") (class "Default")
      (node (ref "P8") (pin "26") (pinfunction "26_26") (pintype "passive"))
      (node (ref "U13") (pin "20") (pinfunction "DIR_20") (pintype "input"))
    )
    (net (code "7") (name "/DIR_Y") (class "Default")
      (node (ref "P8") (pin "19") (pinfunction "19_19") (pintype "passive"))
      (node (ref "U14") (pin "20") (pinfunction "DIR_20") (pintype "input"))
    )
    (net (code "8") (name "/DIR_Z") (class "Default")
      (node (ref "P8") (pin "14") (pinfunction "14_14") (pintype "passive"))
      (node (ref "U15") (pin "20") (pinfunction "DIR_20") (pintype "input"))
    )
    (net (code "9") (name "/END_STOP_X_1") (class "Default")
      (node (ref "P9") (pin "25") (pinfunction "25_25") (pintype "passive"))
      (node (ref "R49") (pin "1") (pinfunction "1_1") (pintype "passive"))
      (node (ref "X23") (pin "2") (pinfunction "S_2") (pintype "passive"))
    )
    (net (code "10") (name "/END_STOP_X_2") (class "Default")
      (node (ref "P9") (pin "11") (pinfunction "11_11") (pintype "passive"))
      (node (ref "R52") (pin "1") (pinfunction "1_1") (pintype "passive"))
      (node (ref "X19") (pin "2") (pinfunction "S_2") (pintype "passive"))
    )
    (net (code "11") (name "/END_STOP_Y_1") (class "Default")
      (node (ref "P9") (pin "23") (pinfunction "23_23") (pintype "passive"))
      (node (ref "R50") (pin "1") (pinfunction "1_1") (pintype "passive"))
      (node (ref "X1") (pin "2") (pinfunction "S_2") (pintype "passive"))
    )
    (net (code "12") (name "/END_STOP_Y_2") (class "Default")
      (node (ref "P9") (pin "16") (pinfunction "16_16") (pintype "passive"))
      (node (ref "R53") (pin "1") (pinfunction "1_1") (pintype "passive"))
      (node (ref "X10") (pin "2") (pinfunction "S_2") (pintype "passive"))
    )
    (net (code "13") (name "/END_STOP_Z_1") (class "Default")
      (node (ref "P9") (pin "13") (pinfunction "13_13") (pintype "passive"))
      (node (ref "R51") (pin "1") (pinfunction "1_1") (pintype "passive"))
      (node (ref "X13") (pin "2") (pinfunction "S_2") (pintype "passive"))
    )
    (net (code "14") (name "/END_STOP_Z_2") (class "Default")
      (node (ref "P9") (pin "18") (pinfunction "18_18") (pintype "passive"))
      (node (ref "R54") (pin "1") (pinfunction "1_1") (pintype "passive"))
      (node (ref "X11") (pin "2") (pinfunction "S_2") (pintype "passive"))
    )
    (net (code "15") (name "/FAN_1") (class "Default")
      (node (ref "Q4") (pin "1") (pinfunction "G_1") (pintype "passive"))
      (node (ref "U11") (pin "15") (pinfunction "LED8_15") (pintype "output"))
    )
    (net (code "16") (name "/FAN_2") (class "Default")
      (node (ref "Q5") (pin "1") (pinfunction "G_1") (pintype "passive"))
      (node (ref "U11") (pin "16") (pinfunction "LED9_16") (pintype "output"))
    )
    (net (code "17") (name "/FAN_3") (class "Default")
      (node (ref "Q6") (pin "1") (pinfunction "G_1") (pintype "passive"))
      (node (ref "U11") (pin "17") (pinfunction "LED10_17") (pintype "output"))
    )
    (net (code "18") (name "/FAULT_EXT1") (class "Default")
      (node (ref "P8") (pin "18") (pinfunction "18_18") (pintype "passive"))
      (node (ref "U16") (pin "18") (pinfunction "FAULT_18") (pintype "output"))
    )
    (net (code "19") (name "/FAULT_EXT2") (class "Default")
      (node (ref "P8") (pin "8") (pinfunction "8_8") (pintype "passive"))
      (node (ref "U17") (pin "18") (pinfunction "FAULT_18") (pintype "output"))
    )
    (net (code "20") (name "/FAULT_X") (class "Default")
      (node (ref "P8") (pin "10") (pinfunction "10_10") (pintype "passive"))
      (node (ref "U13") (pin "18") (pinfunction "FAULT_18") (pintype "output"))
    )
    (net (code "21") (name "/FAULT_Y") (class "Default")
      (node (ref "P8") (pin "9") (pinfunction "9_9") (pintype "passive"))
      (node (ref "U14") (pin "18") (pinfunction "FAULT_18") (pintype "output"))
    )
    (net (code "22") (name "/FAULT_Z") (class "Default")
      (node (ref "P9") (pin "24") (pinfunction "24_24") (pintype "passive"))
      (node (ref "U15") (pin "18") (pinfunction "FAULT_18") (pintype "output"))
    )
    (net (code "23") (name "/HEATER_EXT1") (class "Default")
      (node (ref "R47") (pin "2") (pinfunction "2_2") (pintype "passive"))
      (node (ref "U11") (pin "11") (pinfunction "LED5_11") (pintype "output"))
      (node (ref "U9") (pin "3") (pinfunction "I_3") (pintype "input"))
    )
    (net (code "24") (name "/HEATER_EXT2") (class "Default")
      (node (ref "R48") (pin "2") (pinfunction "2_2") (pintype "passive"))
      (node (ref "U11") (pin "9") (pinfunction "LED3_9") (pintype "output"))
      (node (ref "U7") (pin "3") (pinfunction "I_3") (pintype "input"))
    )
    (net (code "25") (name "/HEATER_HBP") (class "Default")
      (node (ref "R46") (pin "2") (pinfunction "2_2") (pintype "passive"))
      (node (ref "U11") (pin "10") (pinfunction "LED4_10") (pintype "output"))
      (node (ref "U8") (pin "3") (pinfunction "I_3") (pintype "input"))
    )
    (net (code "26") (name "/I2C2_SCL") (class "Default")
      (node (ref "P9") (pin "19") (pinfunction "19_19") (pintype "passive"))
      (node (ref "U11") (pin "26") (pinfunction "SCL_26") (pintype "input"))
      (node (ref "U18") (pin "6") (pinfunction "SCL_6") (pintype "input"))
    )
    (net (code "27") (name "/I2C2_SDA") (class "Default")
      (node (ref "P9") (pin "20") (pinfunction "20_20") (pintype "passive"))
      (node (ref "U11") (pin "27") (pinfunction "SDA_27") (pintype "bidirectional"))
      (node (ref "U18") (pin "5") (pinfunction "SDA_5") (pintype "bidirectional"))
    )
    (net (code "28") (name "/SER_2") (class "Default")
      (node (ref "U1") (pin "9") (pinfunction "QH_2_9") (pintype "output"))
      (node (ref "U2") (pin "14") (pinfunction "SER_14") (pintype "input"))
    )
    (net (code "29") (name "/SER_3") (class "Default")
      (node (ref "U2") (pin "9") (pinfunction "QH_2_9") (pintype "output"))
      (node (ref "U3") (pin "14") (pinfunction "SER_14") (pintype "input"))
    )
    (net (code "30") (name "/SER_4") (class "Default")
      (node (ref "U3") (pin "9") (pinfunction "QH_2_9") (pintype "output"))
      (node (ref "U4") (pin "14") (pinfunction "SER_14") (pintype "input"))
    )
    (net (code "31") (name "/SER_5") (class "Default")
      (node (ref "U4") (pin "9") (pinfunction "QH_2_9") (pintype "output"))
      (node (ref "U5") (pin "14") (pinfunction "SER_14") (pintype "input"))
    )
    (net (code "32") (name "/SPI1_CS0") (class "Default")
      (node (ref "P9") (pin "28") (pinfunction "28_28") (pintype "passive"))
      (node (ref "U12") (pin "15") (pinfunction "P$15-NSYNC_15") (pintype "bidirectional"))
    )
    (net (code "33") (name "/SPI1_CS1") (class "Default")
      (node (ref "P9") (pin "42") (pinfunction "42_42") (pintype "passive"))
      (node (ref "U1") (pin "12") (pinfunction "RCLK_12") (pintype "input"))
      (node (ref "U2") (pin "12") (pinfunction "RCLK_12") (pintype "input"))
      (node (ref "U3") (pin "12") (pinfunction "RCLK_12") (pintype "input"))
      (node (ref "U4") (pin "12") (pinfunction "RCLK_12") (pintype "input"))
      (node (ref "U5") (pin "12") (pinfunction "RCLK_12") (pintype "input"))
    )
    (net (code "34") (name "/SPI1_MISO") (class "Default")
      (node (ref "P9") (pin "29") (pinfunction "29_29") (pintype "passive"))
      (node (ref "U12") (pin "2") (pinfunction "P$2-DOUT_2") (pintype "bidirectional"))
    )
    (net (code "35") (name "/SPI1_MOSI") (class "Default")
      (node (ref "P9") (pin "30") (pinfunction "30_30") (pintype "passive"))
      (node (ref "U1") (pin "14") (pinfunction "SER_14") (pintype "input"))
      (node (ref "U12") (pin "1") (pinfunction "P$1-DIN_1") (pintype "bidirectional"))
    )
    (net (code "36") (name "/SPI1_SCLK") (class "Default")
      (node (ref "P9") (pin "31") (pinfunction "31_31") (pintype "passive"))
      (node (ref "U1") (pin "11") (pinfunction "SRCLK_11") (pintype "input"))
      (node (ref "U12") (pin "16") (pinfunction "P$16-SCLK_16") (pintype "bidirectional"))
      (node (ref "U2") (pin "11") (pinfunction "SRCLK_11") (pintype "input"))
      (node (ref "U3") (pin "11") (pinfunction "SRCLK_11") (pintype "input"))
      (node (ref "U4") (pin "11") (pinfunction "SRCLK_11") (pintype "input"))
      (node (ref "U5") (pin "11") (pinfunction "SRCLK_11") (pintype "input"))
    )
    (net (code "37") (name "/STEP_EXT1") (class "Default")
      (node (ref "P9") (pin "12") (pinfunction "12_12") (pintype "passive"))
      (node (ref "U16") (pin "22") (pinfunction "STEP_22") (pintype "input"))
    )
    (net (code "38") (name "/STEP_EXT2") (class "Default")
      (node (ref "P8") (pin "11") (pinfunction "11_11") (pintype "passive"))
      (node (ref "U17") (pin "22") (pinfunction "STEP_22") (pintype "input"))
    )
    (net (code "39") (name "/STEP_X") (class "Default")
      (node (ref "P8") (pin "17") (pinfunction "17_17") (pintype "passive"))
      (node (ref "U13") (pin "22") (pinfunction "STEP_22") (pintype "input"))
    )
    (net (code "40") (name "/STEP_Y") (class "Default")
      (node (ref "P8") (pin "12") (pinfunction "12_12") (pintype "passive"))
      (node (ref "U14") (pin "22") (pinfunction "STEP_22") (pintype "input"))
    )
    (net (code "41") (name "/STEP_Z") (class "Default")
      (node (ref "P8") (pin "13") (pinfunction "13_13") (pintype "passive"))
      (node (ref "U15") (pin "22") (pinfunction "STEP_22") (pintype "input"))
    )
    (net (code "42") (name "/SYS_5V") (class "Default")
      (node (ref "P9") (pin "7") (pinfunction "7_7") (pintype "passive"))
      (node (ref "P9") (pin "8") (pinfunction "8_8") (pintype "passive"))
    )
    (net (code "43") (name "/TERM_EXT1") (class "Default")
      (node (ref "C26") (pin "1") (pinfunction "1_1") (pintype "passive"))
      (node (ref "P9") (pin "33") (pinfunction "33_33") (pintype "passive"))
      (node (ref "R38") (pin "2") (pinfunction "2_2") (pintype "passive"))
    )
    (net (code "44") (name "/TERM_EXT2") (class "Default")
      (node (ref "C46") (pin "1") (pinfunction "1_1") (pintype "passive"))
      (node (ref "P9") (pin "36") (pinfunction "36_36") (pintype "passive"))
      (node (ref "R40") (pin "2") (pinfunction "2_2") (pintype "passive"))
    )
    (net (code "45") (name "/TERM_HBP") (class "Default")
      (node (ref "C45") (pin "1") (pinfunction "1_1") (pintype "passive"))
      (node (ref "P9") (pin "35") (pinfunction "35_35") (pintype "passive"))
      (node (ref "R39") (pin "2") (pinfunction "2_2") (pintype "passive"))
    )
    (net (code "46") (name "/VDD_12V") (class "Default")
      (node (ref "12V") (pin "TP") (pinfunction "TP_TP") (pintype "input"))
      (node (ref "C20") (pin "1") (pinfunction "1_1") (pintype "passive"))
      (node (ref "C21") (pin "1") (pinfunction "1_1") (pintype "passive"))
      (node (ref "C22") (pin "1") (pinfunction "1_1") (pintype "passive"))
      (node (ref "C23") (pin "1") (pinfunction "1_1") (pintype "passive"))
      (node (ref "C24") (pin "1") (pinfunction "1_1") (pintype "passive"))
      (node (ref "C25") (pin "1") (pinfunction "1_1") (pintype "passive"))
      (node (ref "C53") (pin "1") (pinfunction "1_1") (pintype "passive"))
      (node (ref "L2") (pin "P$1") (pinfunction "P$1_P$1") (pintype "passive"))
      (node (ref "R19") (pin "2") (pinfunction "2_2") (pintype "passive"))
      (node (ref "R20") (pin "2") (pinfunction "2_2") (pintype "passive"))
      (node (ref "R21") (pin "2") (pinfunction "2_2") (pintype "passive"))
      (node (ref "R42") (pin "1") (pinfunction "1_1") (pintype "passive"))
      (node (ref "U7") (pin "2") (pinfunction "VCC_2") (pintype "power_in"))
      (node (ref "U8") (pin "2") (pinfunction "VCC_2") (pintype "power_in"))
      (node (ref "U9") (pin "2") (pinfunction "VCC_2") (pintype "power_in"))
      (node (ref "X4") (pin "1") (pinfunction "S_1") (pintype "passive"))
      (node (ref "X5") (pin "1") (pinfunction "S_1") (pintype "passive"))
      (node (ref "X6") (pin "1") (pinfunction "S_1") (pintype "passive"))
    )
    (net (code "47") (name "/VDD_ADC") (class "Default")
      (node (ref "P9") (pin "32") (pinfunction "32_32") (pintype "passive"))
      (node (ref "R13") (pin "2") (pinfunction "2_2") (pintype "passive"))
      (node (ref "R17") (pin "2") (pinfunction "2_2") (pintype "passive"))
      (node (ref "R18") (pin "2") (pinfunction "2_2") (pintype "passive"))
    )
    (net (code "48") (name "/VDD_IN") (class "Default")
      (node (ref "12..24V") (pin "TP") (pinfunction "TP_TP") (pintype "input"))
      (node (ref "C10") (pin "1") (pinfunction "1_1") (pintype "passive"))
      (node (ref "C12") (pin "+") (pinfunction "+_+") (pintype "passive"))
      (node (ref "C18") (pin "1") (pinfunction "1_1") (pintype "passive"))
      (node (ref "C19") (pin "1") (pinfunction "1_1") (pintype "passive"))
      (node (ref "C2") (pin "1") (pinfunction "1_1") (pintype "passive"))
      (node (ref "C27") (pin "1") (pinfunction "1_1") (pintype "passive"))
      (node (ref "C28") (pin "1") (pinfunction "1_1") (pintype "passive"))
      (node (ref "C29") (pin "1") (pinfunction "1_1") (pintype "passive"))
      (node (ref "C30") (pin "1") (pinfunction "1_1") (pintype "passive"))
      (node (ref "C31") (pin "1") (pinfunction "1_1") (pintype "passive"))
      (node (ref "C32") (pin "1") (pinfunction "1_1") (pintype "passive"))
      (node (ref "C33") (pin "1") (pinfunction "1_1") (pintype "passive"))
      (node (ref "C34") (pin "1") (pinfunction "1_1") (pintype "passive"))
      (node (ref "C35") (pin "1") (pinfunction "1_1") (pintype "passive"))
      (node (ref "C38") (pin "1") (pinfunction "1_1") (pintype "passive"))
      (node (ref "C4") (pin "1") (pinfunction "1_1") (pintype "passive"))
      (node (ref "C42") (pin "1") (pinfunction "1_1") (pintype "passive"))
      (node (ref "C43") (pin "1") (pinfunction "1_1") (pintype "passive"))
      (node (ref "C44") (pin "1") (pinfunction "1_1") (pintype "passive"))
      (node (ref "C47") (pin "1") (pinfunction "1_1") (pintype "passive"))
      (node (ref "C48") (pin "1") (pinfunction "1_1") (pintype "passive"))
      (node (ref "C52") (pin "1") (pinfunction "1_1") (pintype "passive"))
      (node (ref "C6") (pin "1") (pinfunction "1_1") (pintype "passive"))
      (node (ref "C8") (pin "1") (pinfunction "1_1") (pintype "passive"))
      (node (ref "D1") (pin "C") (pinfunction "C_C") (pintype "passive"))
      (node (ref "D2") (pin "C") (pinfunction "C_C") (pintype "passive"))
      (node (ref "D3") (pin "C") (pinfunction "C_C") (pintype "passive"))
      (node (ref "F1") (pin "3") (pinfunction "2_3") (pintype "passive"))
      (node (ref "F1") (pin "4") (pinfunction "2_4") (pintype "passive"))
      (node (ref "R11") (pin "2") (pinfunction "2_2") (pintype "passive"))
      (node (ref "R14") (pin "2") (pinfunction "2_2") (pintype "passive"))
      (node (ref "R15") (pin "2") (pinfunction "2_2") (pintype "passive"))
      (node (ref "R16") (pin "2") (pinfunction "2_2") (pintype "passive"))
      (node (ref "R45") (pin "1") (pinfunction "1_1") (pintype "passive"))
      (node (ref "R55") (pin "2") (pinfunction "2_2") (pintype "passive"))
      (node (ref "R56") (pin "2") (pinfunction "2_2") (pintype "passive"))
      (node (ref "R57") (pin "2") (pinfunction "2_2") (pintype "passive"))
      (node (ref "U10") (pin "4") (pinfunction "VIN_4") (pintype "power_in"))
      (node (ref "U13") (pin "11") (pinfunction "VMB_11") (pintype "power_in"))
      (node (ref "U13") (pin "4") (pinfunction "VMA_4") (pintype "power_in"))
      (node (ref "U14") (pin "11") (pinfunction "VMB_11") (pintype "power_in"))
      (node (ref "U14") (pin "4") (pinfunction "VMA_4") (pintype "power_in"))
      (node (ref "U15") (pin "11") (pinfunction "VMB_11") (pintype "power_in"))
      (node (ref "U15") (pin "4") (pinfunction "VMA_4") (pintype "power_in"))
      (node (ref "U16") (pin "11") (pinfunction "VMB_11") (pintype "power_in"))
      (node (ref "U16") (pin "4") (pinfunction "VMA_4") (pintype "power_in"))
      (node (ref "U17") (pin "11") (pinfunction "VMB_11") (pintype "power_in"))
      (node (ref "U17") (pin "4") (pinfunction "VMA_4") (pintype "power_in"))
      (node (ref "U6") (pin "11") (pinfunction "VIN_11") (pintype "power_in"))
      (node (ref "U6") (pin "2") (pinfunction "VIN_2") (pintype "power_in"))
      (node (ref "U6") (pin "3") (pinfunction "VIN_3") (pintype "power_in"))
      (node (ref "X20") (pin "1") (pinfunction "1_1") (pintype "passive"))
      (node (ref "X20") (pin "2") (pinfunction "1_2") (pintype "passive"))
      (node (ref "X21") (pin "1") (pinfunction "1_1") (pintype "passive"))
      (node (ref "X3") (pin "1") (pinfunction "1_1") (pintype "passive"))
    )
    (net (code "49") (name "/VIN") (class "Default")
      (node (ref "F1") (pin "1") (pinfunction "1_1") (pintype "passive"))
      (node (ref "F1") (pin "2") (pinfunction "1_2") (pintype "passive"))
      (node (ref "LED8") (pin "A") (pinfunction "A_A") (pintype "passive"))
      (node (ref "X2") (pin "3") (pinfunction "1_3") (pintype "passive"))
      (node (ref "X2") (pin "4") (pinfunction "1_4") (pintype "passive"))
    )
    (net (code "50") (name "/VREF_EXT1") (class "Default")
      (node (ref "U12") (pin "6") (pinfunction "P$6-VOUTD_6") (pintype "bidirectional"))
      (node (ref "U16") (pin "12") (pinfunction "AVREF_12") (pintype "input"))
      (node (ref "U16") (pin "13") (pinfunction "BVREF_13") (pintype "input"))
    )
    (net (code "51") (name "/VREF_EXT2") (class "Default")
      (node (ref "U12") (pin "14") (pinfunction "P$14-VOUTE_14") (pintype "bidirectional"))
      (node (ref "U17") (pin "12") (pinfunction "AVREF_12") (pintype "input"))
      (node (ref "U17") (pin "13") (pinfunction "BVREF_13") (pintype "input"))
    )
    (net (code "52") (name "/VREF_X") (class "Default")
      (node (ref "U12") (pin "3") (pinfunction "P$3-VOUTA_3") (pintype "bidirectional"))
      (node (ref "U13") (pin "12") (pinfunction "AVREF_12") (pintype "input"))
      (node (ref "U13") (pin "13") (pinfunction "BVREF_13") (pintype "input"))
    )
    (net (code "53") (name "/VREF_Y") (class "Default")
      (node (ref "U12") (pin "4") (pinfunction "P$4-VOUTB_4") (pintype "bidirectional"))
      (node (ref "U14") (pin "12") (pinfunction "AVREF_12") (pintype "input"))
      (node (ref "U14") (pin "13") (pinfunction "BVREF_13") (pintype "input"))
    )
    (net (code "54") (name "/VREF_Z") (class "Default")
      (node (ref "U12") (pin "5") (pinfunction "P$5-VOUTC_5") (pintype "bidirectional"))
      (node (ref "U15") (pin "12") (pinfunction "AVREF_12") (pintype "input"))
      (node (ref "U15") (pin "13") (pinfunction "BVREF_13") (pintype "input"))
    )
    (net (code "55") (name "AGND") (class "Default")
      (node (ref "C14") (pin "2") (pinfunction "2_2") (pintype "passive"))
      (node (ref "C15") (pin "2") (pinfunction "2_2") (pintype "passive"))
      (node (ref "C16") (pin "2") (pinfunction "2_2") (pintype "passive"))
      (node (ref "C26") (pin "2") (pinfunction "2_2") (pintype "passive"))
      (node (ref "C45") (pin "2") (pinfunction "2_2") (pintype "passive"))
      (node (ref "C46") (pin "2") (pinfunction "2_2") (pintype "passive"))
      (node (ref "P9") (pin "34") (pinfunction "34_34") (pintype "passive"))
      (node (ref "X7") (pin "2") (pinfunction "S_2") (pintype "passive"))
      (node (ref "X8") (pin "2") (pinfunction "S_2") (pintype "passive"))
      (node (ref "X9") (pin "2") (pinfunction "S_2") (pintype "passive"))
    )
    (net (code "56") (name "GND") (class "Default")
      (node (ref "C11") (pin "2") (pinfunction "2_2") (pintype "passive"))
      (node (ref "C12") (pin "-") (pinfunction "-_-") (pintype "passive"))
      (node (ref "C13") (pin "2") (pinfunction "2_2") (pintype "passive"))
      (node (ref "C17") (pin "2") (pinfunction "2_2") (pintype "passive"))
      (node (ref "C18") (pin "2") (pinfunction "2_2") (pintype "passive"))
      (node (ref "C19") (pin "2") (pinfunction "2_2") (pintype "passive"))
      (node (ref "C20") (pin "2") (pinfunction "2_2") (pintype "passive"))
      (node (ref "C21") (pin "2") (pinfunction "2_2") (pintype "passive"))
      (node (ref "C22") (pin "2") (pinfunction "2_2") (pintype "passive"))
      (node (ref "C23") (pin "2") (pinfunction "2_2") (pintype "passive"))
      (node (ref "C24") (pin "2") (pinfunction "2_2") (pintype "passive"))
      (node (ref "C25") (pin "2") (pinfunction "2_2") (pintype "passive"))
      (node (ref "C27") (pin "2") (pinfunction "2_2") (pintype "passive"))
      (node (ref "C28") (pin "2") (pinfunction "2_2") (pintype "passive"))
      (node (ref "C29") (pin "2") (pinfunction "2_2") (pintype "passive"))
      (node (ref "C30") (pin "2") (pinfunction "2_2") (pintype "passive"))
      (node (ref "C31") (pin "2") (pinfunction "2_2") (pintype "passive"))
      (node (ref "C32") (pin "2") (pinfunction "2_2") (pintype "passive"))
      (node (ref "C33") (pin "2") (pinfunction "2_2") (pintype "passive"))
      (node (ref "C34") (pin "2") (pinfunction "2_2") (pintype "passive"))
      (node (ref "C35") (pin "2") (pinfunction "2_2") (pintype "passive"))
      (node (ref "C36") (pin "2") (pinfunction "2_2") (pintype "passive"))
      (node (ref "C37") (pin "2") (pinfunction "2_2") (pintype "passive"))
      (node (ref "C38") (pin "2") (pinfunction "2_2") (pintype "passive"))
      (node (ref "C39") (pin "2") (pinfunction "2_2") (pintype "passive"))
      (node (ref "C40") (pin "2") (pinfunction "2_2") (pintype "passive"))
      (node (ref "C41") (pin "2") (pinfunction "2_2") (pintype "passive"))
      (node (ref "C42") (pin "2") (pinfunction "2_2") (pintype "passive"))
      (node (ref "C43") (pin "2") (pinfunction "2_2") (pintype "passive"))
      (node (ref "C44") (pin "2") (pinfunction "2_2") (pintype "passive"))
      (node (ref "C47") (pin "2") (pinfunction "2_2") (pintype "passive"))
      (node (ref "C48") (pin "2") (pinfunction "2_2") (pintype "passive"))
      (node (ref "C49") (pin "2") (pinfunction "2_2") (pintype "passive"))
      (node (ref "C50") (pin "2") (pinfunction "2_2") (pintype "passive"))
      (node (ref "C52") (pin "2") (pinfunction "2_2") (pintype "passive"))
      (node (ref "C53") (pin "2") (pinfunction "2_2") (pintype "passive"))
      (node (ref "C54") (pin "2") (pinfunction "2_2") (pintype "passive"))
      (node (ref "C57") (pin "2") (pinfunction "2_2") (pintype "passive"))
      (node (ref "C58") (pin "2") (pinfunction "2_2") (pintype "passive"))
      (node (ref "C59") (pin "2") (pinfunction "2_2") (pintype "passive"))
      (node (ref "C60") (pin "2") (pinfunction "2_2") (pintype "passive"))
      (node (ref "C61") (pin "-") (pinfunction "-_-") (pintype "passive"))
      (node (ref "D4") (pin "A") (pinfunction "A_A") (pintype "passive"))
      (node (ref "LED4") (pin "C") (pinfunction "C_C") (pintype "passive"))
      (node (ref "P8") (pin "1") (pinfunction "1_1") (pintype "passive"))
      (node (ref "P8") (pin "2") (pinfunction "2_2") (pintype "passive"))
      (node (ref "P9") (pin "1") (pinfunction "1_1") (pintype "passive"))
      (node (ref "P9") (pin "2") (pinfunction "2_2") (pintype "passive"))
      (node (ref "P9") (pin "43") (pinfunction "43_43") (pintype "passive"))
      (node (ref "P9") (pin "44") (pinfunction "44_44") (pintype "passive"))
      (node (ref "P9") (pin "45") (pinfunction "45_45") (pintype "passive"))
      (node (ref "P9") (pin "46") (pinfunction "46_46") (pintype "passive"))
      (node (ref "Q1") (pin "1") (pinfunction "S_1") (pintype "passive"))
      (node (ref "Q1") (pin "2") (pinfunction "S_2") (pintype "passive"))
      (node (ref "Q1") (pin "3") (pinfunction "S_3") (pintype "passive"))
      (node (ref "Q2") (pin "1") (pinfunction "S_1") (pintype "passive"))
      (node (ref "Q2") (pin "2") (pinfunction "S_2") (pintype "passive"))
      (node (ref "Q2") (pin "3") (pinfunction "S_3") (pintype "passive"))
      (node (ref "Q3") (pin "1") (pinfunction "S_1") (pintype "passive"))
      (node (ref "Q3") (pin "2") (pinfunction "S_2") (pintype "passive"))
      (node (ref "Q3") (pin "3") (pinfunction "S_3") (pintype "passive"))
      (node (ref "Q4") (pin "3") (pinfunction "S_3") (pintype "passive"))
      (node (ref "Q5") (pin "3") (pinfunction "S_3") (pintype "passive"))
      (node (ref "Q6") (pin "3") (pinfunction "S_3") (pintype "passive"))
      (node (ref "R1") (pin "1") (pinfunction "1_1") (pintype "passive"))
      (node (ref "R10") (pin "1") (pinfunction "1_1") (pintype "passive"))
      (node (ref "R2") (pin "1") (pinfunction "1_1") (pintype "passive"))
      (node (ref "R3") (pin "1") (pinfunction "1_1") (pintype "passive"))
      (node (ref "R4") (pin "1") (pinfunction "1_1") (pintype "passive"))
      (node (ref "R43") (pin "2") (pinfunction "2_2") (pintype "passive"))
      (node (ref "R44") (pin "2") (pinfunction "2_2") (pintype "passive"))
      (node (ref "R46") (pin "1") (pinfunction "1_1") (pintype "passive"))
      (node (ref "R47") (pin "1") (pinfunction "1_1") (pintype "passive"))
      (node (ref "R48") (pin "1") (pinfunction "1_1") (pintype "passive"))
      (node (ref "R5") (pin "1") (pinfunction "1_1") (pintype "passive"))
      (node (ref "R6") (pin "1") (pinfunction "1_1") (pintype "passive"))
      (node (ref "R7") (pin "1") (pinfunction "1_1") (pintype "passive"))
      (node (ref "R8") (pin "1") (pinfunction "1_1") (pintype "passive"))
      (node (ref "R9") (pin "1") (pinfunction "1_1") (pintype "passive"))
      (node (ref "S2") (pin "1") (pinfunction "1_1") (pintype "passive"))
      (node (ref "S2") (pin "2") (pinfunction "2_2") (pintype "passive"))
      (node (ref "U1") (pin "13") (pinfunction "~{OE}_13") (pintype "input"))
      (node (ref "U1") (pin "8") (pinfunction "GND_8") (pintype "passive"))
      (node (ref "U10") (pin "6") (pinfunction "GND_6") (pintype "power_in"))
      (node (ref "U10") (pin "EP") (pinfunction "EP_EP") (pintype "power_in"))
      (node (ref "U11") (pin "14") (pinfunction "VSS_14") (pintype "passive"))
      (node (ref "U11") (pin "23") (pinfunction "~{OE}_23") (pintype "input"))
      (node (ref "U12") (pin "10") (pinfunction "P$10-GND_10") (pintype "bidirectional"))
      (node (ref "U13") (pin "14") (pinfunction "GND_0_14") (pintype "power_in"))
      (node (ref "U13") (pin "28") (pinfunction "GND_1_28") (pintype "power_in"))
      (node (ref "U13") (pin "EXP") (pinfunction "GND_PAD_EXP") (pintype "power_in"))
      (node (ref "U14") (pin "14") (pinfunction "GND_0_14") (pintype "power_in"))
      (node (ref "U14") (pin "28") (pinfunction "GND_1_28") (pintype "power_in"))
      (node (ref "U14") (pin "EXP") (pinfunction "GND_PAD_EXP") (pintype "power_in"))
      (node (ref "U15") (pin "14") (pinfunction "GND_0_14") (pintype "power_in"))
      (node (ref "U15") (pin "28") (pinfunction "GND_1_28") (pintype "power_in"))
      (node (ref "U15") (pin "EXP") (pinfunction "GND_PAD_EXP") (pintype "power_in"))
      (node (ref "U16") (pin "14") (pinfunction "GND_0_14") (pintype "power_in"))
      (node (ref "U16") (pin "28") (pinfunction "GND_1_28") (pintype "power_in"))
      (node (ref "U16") (pin "EXP") (pinfunction "GND_PAD_EXP") (pintype "power_in"))
      (node (ref "U17") (pin "14") (pinfunction "GND_0_14") (pintype "power_in"))
      (node (ref "U17") (pin "28") (pinfunction "GND_1_28") (pintype "power_in"))
      (node (ref "U17") (pin "EXP") (pinfunction "GND_PAD_EXP") (pintype "power_in"))
      (node (ref "U18") (pin "4") (pinfunction "GND_4") (pintype "power_in"))
      (node (ref "U2") (pin "13") (pinfunction "~{OE}_13") (pintype "input"))
      (node (ref "U2") (pin "8") (pinfunction "GND_8") (pintype "passive"))
      (node (ref "U3") (pin "13") (pinfunction "~{OE}_13") (pintype "input"))
      (node (ref "U3") (pin "8") (pinfunction "GND_8") (pintype "passive"))
      (node (ref "U4") (pin "13") (pinfunction "~{OE}_13") (pintype "input"))
      (node (ref "U4") (pin "8") (pinfunction "GND_8") (pintype "passive"))
      (node (ref "U5") (pin "13") (pinfunction "~{OE}_13") (pintype "input"))
      (node (ref "U5") (pin "8") (pinfunction "GND_8") (pintype "passive"))
      (node (ref "U6") (pin "14") (pinfunction "PGND_14") (pintype "power_in"))
      (node (ref "U6") (pin "15") (pinfunction "PGND_15") (pintype "power_in"))
      (node (ref "U6") (pin "4") (pinfunction "SGND_4") (pintype "power_in"))
      (node (ref "U6") (pin "P$17") (pinfunction "EP_P$17") (pintype "power_in"))
      (node (ref "U7") (pin "1") (pinfunction "GND_1") (pintype "power_in"))
      (node (ref "U7") (pin "4") (pinfunction "GND_4") (pintype "power_in"))
      (node (ref "U8") (pin "1") (pinfunction "GND_1") (pintype "power_in"))
      (node (ref "U8") (pin "4") (pinfunction "GND_4") (pintype "power_in"))
      (node (ref "U9") (pin "1") (pinfunction "GND_1") (pintype "power_in"))
      (node (ref "U9") (pin "4") (pinfunction "GND_4") (pintype "power_in"))
      (node (ref "X1") (pin "1") (pinfunction "S_1") (pintype "passive"))
      (node (ref "X10") (pin "1") (pinfunction "S_1") (pintype "passive"))
      (node (ref "X11") (pin "1") (pinfunction "S_1") (pintype "passive"))
      (node (ref "X12") (pin "3") (pinfunction "S_3") (pintype "passive"))
      (node (ref "X13") (pin "1") (pinfunction "S_1") (pintype "passive"))
      (node (ref "X19") (pin "1") (pinfunction "S_1") (pintype "passive"))
      (node (ref "X2") (pin "1") (pinfunction "1_1") (pintype "passive"))
      (node (ref "X2") (pin "2") (pinfunction "1_2") (pintype "passive"))
      (node (ref "X23") (pin "1") (pinfunction "S_1") (pintype "passive"))
      (node (ref "X7") (pin "3") (pinfunction "S_3") (pintype "passive"))
      (node (ref "X8") (pin "3") (pinfunction "S_3") (pintype "passive"))
      (node (ref "X9") (pin "3") (pinfunction "S_3") (pintype "passive"))
    )
    (net (code "57") (name "Net-(C51-Pad2)") (class "Default")
      (node (ref "C51") (pin "2") (pinfunction "2_2") (pintype "passive"))
      (node (ref "L1") (pin "1") (pinfunction "1_1") (pintype "passive"))
      (node (ref "U6") (pin "1") (pinfunction "SW_1") (pintype "power_in"))
      (node (ref "U6") (pin "12") (pinfunction "SW_12") (pintype "power_in"))
      (node (ref "U6") (pin "13") (pinfunction "SW_13") (pintype "power_in"))
      (node (ref "U6") (pin "16") (pinfunction "SW_16") (pintype "power_in"))
    )
    (net (code "58") (name "Net-(C56-Pad2)") (class "Default")
      (node (ref "C56") (pin "2") (pinfunction "2_2") (pintype "passive"))
      (node (ref "R44") (pin "1") (pinfunction "1_1") (pintype "passive"))
    )
    (net (code "59") (name "Net-(LED1-PadA)") (class "Default")
      (node (ref "LED1") (pin "A") (pinfunction "A_A") (pintype "passive"))
      (node (ref "R14") (pin "1") (pinfunction "1_1") (pintype "passive"))
    )
    (net (code "60") (name "Net-(LED2-PadA)") (class "Default")
      (node (ref "LED2") (pin "A") (pinfunction "A_A") (pintype "passive"))
      (node (ref "R16") (pin "1") (pinfunction "1_1") (pintype "passive"))
    )
    (net (code "61") (name "Net-(LED3-PadA)") (class "Default")
      (node (ref "LED3") (pin "A") (pinfunction "A_A") (pintype "passive"))
      (node (ref "R15") (pin "1") (pinfunction "1_1") (pintype "passive"))
    )
    (net (code "62") (name "Net-(LED4-PadA)") (class "Default")
      (node (ref "LED4") (pin "A") (pinfunction "A_A") (pintype "passive"))
      (node (ref "R11") (pin "1") (pinfunction "1_1") (pintype "passive"))
    )
    (net (code "63") (name "Net-(LED5-PadA)") (class "Default")
      (node (ref "LED5") (pin "A") (pinfunction "A_A") (pintype "passive"))
      (node (ref "R19") (pin "1") (pinfunction "1_1") (pintype "passive"))
    )
    (net (code "64") (name "Net-(LED6-PadA)") (class "Default")
      (node (ref "LED6") (pin "A") (pinfunction "A_A") (pintype "passive"))
      (node (ref "R20") (pin "1") (pinfunction "1_1") (pintype "passive"))
    )
    (net (code "65") (name "Net-(LED7-PadA)") (class "Default")
      (node (ref "LED7") (pin "A") (pinfunction "A_A") (pintype "passive"))
      (node (ref "R21") (pin "1") (pinfunction "1_1") (pintype "passive"))
    )
    (net (code "66") (name "Net-(LED8-PadC)") (class "Default")
      (node (ref "LED8") (pin "C") (pinfunction "C_C") (pintype "passive"))
      (node (ref "R45") (pin "2") (pinfunction "2_2") (pintype "passive"))
    )
    (net (code "67") (name "Net-(Q1-G)") (class "Default")
      (node (ref "Q1") (pin "4") (pinfunction "G_4") (pintype "passive"))
      (node (ref "R31") (pin "1") (pinfunction "1_1") (pintype "passive"))
    )
    (net (code "68") (name "Net-(Q2-G)") (class "Default")
      (node (ref "Q2") (pin "4") (pinfunction "G_4") (pintype "passive"))
      (node (ref "R37") (pin "1") (pinfunction "1_1") (pintype "passive"))
    )
    (net (code "69") (name "Net-(Q3-G)") (class "Default")
      (node (ref "Q3") (pin "4") (pinfunction "G_4") (pintype "passive"))
      (node (ref "R32") (pin "1") (pinfunction "1_1") (pintype "passive"))
    )
    (net (code "70") (name "Net-(U1-QB)") (class "Default")
      (node (ref "U1") (pin "1") (pinfunction "QB_1") (pintype "output"))
      (node (ref "U13") (pin "26") (pinfunction "MODE2_26") (pintype "input"))
    )
    (net (code "71") (name "Net-(U1-QC)") (class "Default")
      (node (ref "U1") (pin "2") (pinfunction "QC_2") (pintype "output"))
      (node (ref "U13") (pin "25") (pinfunction "MODE1_25") (pintype "input"))
    )
    (net (code "72") (name "Net-(U1-QD)") (class "Default")
      (node (ref "U1") (pin "3") (pinfunction "QD_3") (pintype "output"))
      (node (ref "U13") (pin "24") (pinfunction "MODE0_24") (pintype "input"))
    )
    (net (code "73") (name "Net-(U1-QE)") (class "Default")
      (node (ref "U1") (pin "4") (pinfunction "QE_4") (pintype "output"))
      (node (ref "U13") (pin "21") (pinfunction "ENBL_21") (pintype "input"))
    )
    (net (code "74") (name "Net-(U1-QF)") (class "Default")
      (node (ref "U1") (pin "5") (pinfunction "QF_5") (pintype "output"))
      (node (ref "U13") (pin "19") (pinfunction "DECAY_19") (pintype "input"))
    )
    (net (code "75") (name "Net-(U1-QG)") (class "Default")
      (node (ref "U1") (pin "6") (pinfunction "QG_6") (pintype "output"))
      (node (ref "U13") (pin "17") (pinfunction "SLEEP_17") (pintype "input"))
    )
    (net (code "76") (name "Net-(U1-QH)") (class "Default")
      (node (ref "U1") (pin "7") (pinfunction "QH_7") (pintype "output"))
      (node (ref "U13") (pin "16") (pinfunction "RESET_16") (pintype "input"))
    )
    (net (code "77") (name "Net-(U1-~{SRCLR})") (class "Default")
      (node (ref "R12") (pin "1") (pinfunction "1_1") (pintype "passive"))
      (node (ref "U1") (pin "10") (pinfunction "~{SRCLR}_10") (pintype "input"))
    )
    (net (code "78") (name "Net-(U2-~{SRCLR})") (class "Default")
      (node (ref "R35") (pin "1") (pinfunction "1_1") (pintype "passive"))
      (node (ref "U2") (pin "10") (pinfunction "~{SRCLR}_10") (pintype "input"))
    )
    (net (code "79") (name "Net-(U3-~{SRCLR})") (class "Default")
      (node (ref "R36") (pin "1") (pinfunction "1_1") (pintype "passive"))
      (node (ref "U3") (pin "10") (pinfunction "~{SRCLR}_10") (pintype "input"))
    )
    (net (code "80") (name "Net-(U4-~{SRCLR})") (class "Default")
      (node (ref "R33") (pin "1") (pinfunction "1_1") (pintype "passive"))
      (node (ref "U4") (pin "10") (pinfunction "~{SRCLR}_10") (pintype "input"))
    )
    (net (code "81") (name "Net-(U5-~{SRCLR})") (class "Default")
      (node (ref "R34") (pin "1") (pinfunction "1_1") (pintype "passive"))
      (node (ref "U5") (pin "10") (pinfunction "~{SRCLR}_10") (pintype "input"))
    )
    (net (code "82") (name "Net-(U6-BOOST)") (class "Default")
      (node (ref "C51") (pin "1") (pinfunction "1_1") (pintype "passive"))
      (node (ref "U6") (pin "10") (pinfunction "BOOST_10") (pintype "bidirectional"))
    )
    (net (code "83") (name "Net-(U6-PG)") (class "Default")
      (node (ref "R41") (pin "1") (pinfunction "1_1") (pintype "passive"))
      (node (ref "U6") (pin "8") (pinfunction "PG_8") (pintype "output"))
    )
    (net (code "84") (name "Net-(U7-O)") (class "Default")
      (node (ref "R37") (pin "2") (pinfunction "2_2") (pintype "passive"))
      (node (ref "U7") (pin "5") (pinfunction "O_5") (pintype "output"))
    )
    (net (code "85") (name "Net-(U8-O)") (class "Default")
      (node (ref "R31") (pin "2") (pinfunction "2_2") (pintype "passive"))
      (node (ref "U8") (pin "5") (pinfunction "O_5") (pintype "output"))
    )
    (net (code "86") (name "Net-(U9-O)") (class "Default")
      (node (ref "R32") (pin "2") (pinfunction "2_2") (pintype "passive"))
      (node (ref "U9") (pin "5") (pinfunction "O_5") (pintype "output"))
    )
    (net (code "87") (name "Net-(U10-BOOT)") (class "Default")
      (node (ref "C55") (pin "1") (pinfunction "1_1") (pintype "passive"))
      (node (ref "U10") (pin "2") (pinfunction "BOOT_2") (pintype "input"))
    )
    (net (code "88") (name "Net-(U10-COMP)") (class "Default")
      (node (ref "C56") (pin "1") (pinfunction "1_1") (pintype "passive"))
      (node (ref "U10") (pin "8") (pinfunction "COMP_8") (pintype "bidirectional"))
    )
    (net (code "89") (name "Net-(U10-FB)") (class "Default")
      (node (ref "R42") (pin "2") (pinfunction "2_2") (pintype "passive"))
      (node (ref "R43") (pin "1") (pinfunction "1_1") (pintype "passive"))
      (node (ref "U10") (pin "7") (pinfunction "FB_7") (pintype "input"))
    )
    (net (code "90") (name "Net-(U10-SS)") (class "Default")
      (node (ref "C54") (pin "1") (pinfunction "1_1") (pintype "passive"))
      (node (ref "U10") (pin "10") (pinfunction "SS_10") (pintype "bidirectional"))
    )
    (net (code "91") (name "Net-(U10-SW)") (class "Default")
      (node (ref "C55") (pin "2") (pinfunction "2_2") (pintype "passive"))
      (node (ref "D4") (pin "C") (pinfunction "C_C") (pintype "passive"))
      (node (ref "L2") (pin "P$2") (pinfunction "P$2_P$2") (pintype "passive"))
      (node (ref "U10") (pin "5") (pinfunction "SW_5") (pintype "power_in"))
    )
    (net (code "92") (name "Net-(U11-A0)") (class "Default")
      (node (ref "R27") (pin "1") (pinfunction "1_1") (pintype "passive"))
      (node (ref "U11") (pin "1") (pinfunction "A0_1") (pintype "input"))
    )
    (net (code "93") (name "Net-(U11-A1)") (class "Default")
      (node (ref "R26") (pin "1") (pinfunction "1_1") (pintype "passive"))
      (node (ref "U11") (pin "2") (pinfunction "A1_2") (pintype "input"))
    )
    (net (code "94") (name "Net-(U11-A2)") (class "Default")
      (node (ref "R25") (pin "1") (pinfunction "1_1") (pintype "passive"))
      (node (ref "U11") (pin "3") (pinfunction "A2_3") (pintype "input"))
    )
    (net (code "95") (name "Net-(U11-A3)") (class "Default")
      (node (ref "R28") (pin "1") (pinfunction "1_1") (pintype "passive"))
      (node (ref "U11") (pin "4") (pinfunction "A3_4") (pintype "input"))
    )
    (net (code "96") (name "Net-(U11-A4)") (class "Default")
      (node (ref "R29") (pin "1") (pinfunction "1_1") (pintype "passive"))
      (node (ref "U11") (pin "5") (pinfunction "A4_5") (pintype "input"))
    )
    (net (code "97") (name "Net-(U11-A5)") (class "Default")
      (node (ref "R30") (pin "1") (pinfunction "1_1") (pintype "passive"))
      (node (ref "U11") (pin "24") (pinfunction "A5_24") (pintype "input"))
    )
    (net (code "98") (name "Net-(U13-AOUT1)") (class "Default")
      (node (ref "U13") (pin "5") (pinfunction "AOUT1_5") (pintype "output"))
      (node (ref "X14") (pin "4") (pinfunction "S_4") (pintype "passive"))
    )
    (net (code "99") (name "Net-(U13-AOUT2)") (class "Default")
      (node (ref "U13") (pin "7") (pinfunction "AOUT2_7") (pintype "output"))
      (node (ref "X14") (pin "3") (pinfunction "S_3") (pintype "passive"))
    )
    (net (code "100") (name "Net-(U13-BOUT1)") (class "Default")
      (node (ref "U13") (pin "10") (pinfunction "BOUT1_10") (pintype "output"))
      (node (ref "X14") (pin "2") (pinfunction "S_2") (pintype "passive"))
    )
    (net (code "101") (name "Net-(U13-BOUT2)") (class "Default")
      (node (ref "U13") (pin "8") (pinfunction "BOUT2_8") (pintype "output"))
      (node (ref "X14") (pin "1") (pinfunction "S_1") (pintype "passive"))
    )
    (net (code "102") (name "Net-(U13-CP1)") (class "Default")
      (node (ref "C1") (pin "2") (pinfunction "2_2") (pintype "passive"))
      (node (ref "U13") (pin "1") (pinfunction "CP1_1") (pintype "bidirectional"))
    )
    (net (code "103") (name "Net-(U13-CP2)") (class "Default")
      (node (ref "C1") (pin "1") (pinfunction "1_1") (pintype "passive"))
      (node (ref "U13") (pin "2") (pinfunction "CP2_2") (pintype "bidirectional"))
    )
    (net (code "104") (name "Net-(U13-ISENA)") (class "Default")
      (node (ref "R2") (pin "2") (pinfunction "2_2") (pintype "passive"))
      (node (ref "U13") (pin "6") (pinfunction "ISENA_6") (pintype "output"))
    )
    (net (code "105") (name "Net-(U13-ISENB)") (class "Default")
      (node (ref "R1") (pin "2") (pinfunction "2_2") (pintype "passive"))
      (node (ref "U13") (pin "9") (pinfunction "ISENB_9") (pintype "output"))
    )
    (net (code "106") (name "Net-(U13-VCP)") (class "Default")
      (node (ref "C2") (pin "2") (pinfunction "2_2") (pintype "passive"))
      (node (ref "U13") (pin "3") (pinfunction "VCP_3") (pintype "bidirectional"))
    )
    (net (code "107") (name "Net-(U14-AOUT1)") (class "Default")
      (node (ref "U14") (pin "5") (pinfunction "AOUT1_5") (pintype "output"))
      (node (ref "X15") (pin "4") (pinfunction "S_4") (pintype "passive"))
    )
    (net (code "108") (name "Net-(U14-AOUT2)") (class "Default")
      (node (ref "U14") (pin "7") (pinfunction "AOUT2_7") (pintype "output"))
      (node (ref "X15") (pin "3") (pinfunction "S_3") (pintype "passive"))
    )
    (net (code "109") (name "Net-(U14-BOUT1)") (class "Default")
      (node (ref "U14") (pin "10") (pinfunction "BOUT1_10") (pintype "output"))
      (node (ref "X15") (pin "2") (pinfunction "S_2") (pintype "passive"))
    )
    (net (code "110") (name "Net-(U14-BOUT2)") (class "Default")
      (node (ref "U14") (pin "8") (pinfunction "BOUT2_8") (pintype "output"))
      (node (ref "X15") (pin "1") (pinfunction "S_1") (pintype "passive"))
    )
    (net (code "111") (name "Net-(U14-CP1)") (class "Default")
      (node (ref "C3") (pin "2") (pinfunction "2_2") (pintype "passive"))
      (node (ref "U14") (pin "1") (pinfunction "CP1_1") (pintype "bidirectional"))
    )
    (net (code "112") (name "Net-(U14-CP2)") (class "Default")
      (node (ref "C3") (pin "1") (pinfunction "1_1") (pintype "passive"))
      (node (ref "U14") (pin "2") (pinfunction "CP2_2") (pintype "bidirectional"))
    )
    (net (code "113") (name "Net-(U14-DECAY)") (class "Default")
      (node (ref "U14") (pin "19") (pinfunction "DECAY_19") (pintype "input"))
      (node (ref "U2") (pin "5") (pinfunction "QF_5") (pintype "output"))
    )
    (net (code "114") (name "Net-(U14-ENBL)") (class "Default")
      (node (ref "U14") (pin "21") (pinfunction "ENBL_21") (pintype "input"))
      (node (ref "U2") (pin "4") (pinfunction "QE_4") (pintype "output"))
    )
    (net (code "115") (name "Net-(U14-ISENA)") (class "Default")
      (node (ref "R4") (pin "2") (pinfunction "2_2") (pintype "passive"))
      (node (ref "U14") (pin "6") (pinfunction "ISENA_6") (pintype "output"))
    )
    (net (code "116") (name "Net-(U14-ISENB)") (class "Default")
      (node (ref "R3") (pin "2") (pinfunction "2_2") (pintype "passive"))
      (node (ref "U14") (pin "9") (pinfunction "ISENB_9") (pintype "output"))
    )
    (net (code "117") (name "Net-(U14-MODE0)") (class "Default")
      (node (ref "U14") (pin "24") (pinfunction "MODE0_24") (pintype "input"))
      (node (ref "U2") (pin "3") (pinfunction "QD_3") (pintype "output"))
    )
    (net (code "118") (name "Net-(U14-MODE1)") (class "Default")
      (node (ref "U14") (pin "25") (pinfunction "MODE1_25") (pintype "input"))
      (node (ref "U2") (pin "2") (pinfunction "QC_2") (pintype "output"))
    )
    (net (code "119") (name "Net-(U14-MODE2)") (class "Default")
      (node (ref "U14") (pin "26") (pinfunction "MODE2_26") (pintype "input"))
      (node (ref "U2") (pin "1") (pinfunction "QB_1") (pintype "output"))
    )
    (net (code "120") (name "Net-(U14-RESET)") (class "Default")
      (node (ref "U14") (pin "16") (pinfunction "RESET_16") (pintype "input"))
      (node (ref "U2") (pin "7") (pinfunction "QH_7") (pintype "output"))
    )
    (net (code "121") (name "Net-(U14-SLEEP)") (class "Default")
      (node (ref "U14") (pin "17") (pinfunction "SLEEP_17") (pintype "input"))
      (node (ref "U2") (pin "6") (pinfunction "QG_6") (pintype "output"))
    )
    (net (code "122") (name "Net-(U14-VCP)") (class "Default")
      (node (ref "C4") (pin "2") (pinfunction "2_2") (pintype "passive"))
      (node (ref "U14") (pin "3") (pinfunction "VCP_3") (pintype "bidirectional"))
    )
    (net (code "123") (name "Net-(U15-AOUT1)") (class "Default")
      (node (ref "U15") (pin "5") (pinfunction "AOUT1_5") (pintype "output"))
      (node (ref "X16") (pin "4") (pinfunction "S_4") (pintype "passive"))
    )
    (net (code "124") (name "Net-(U15-AOUT2)") (class "Default")
      (node (ref "U15") (pin "7") (pinfunction "AOUT2_7") (pintype "output"))
      (node (ref "X16") (pin "3") (pinfunction "S_3") (pintype "passive"))
    )
    (net (code "125") (name "Net-(U15-BOUT1)") (class "Default")
      (node (ref "U15") (pin "10") (pinfunction "BOUT1_10") (pintype "output"))
      (node (ref "X16") (pin "2") (pinfunction "S_2") (pintype "passive"))
    )
    (net (code "126") (name "Net-(U15-BOUT2)") (class "Default")
      (node (ref "U15") (pin "8") (pinfunction "BOUT2_8") (pintype "output"))
      (node (ref "X16") (pin "1") (pinfunction "S_1") (pintype "passive"))
    )
    (net (code "127") (name "Net-(U15-CP1)") (class "Default")
      (node (ref "C5") (pin "2") (pinfunction "2_2") (pintype "passive"))
      (node (ref "U15") (pin "1") (pinfunction "CP1_1") (pintype "bidirectional"))
    )
    (net (code "128") (name "Net-(U15-CP2)") (class "Default")
      (node (ref "C5") (pin "1") (pinfunction "1_1") (pintype "passive"))
      (node (ref "U15") (pin "2") (pinfunction "CP2_2") (pintype "bidirectional"))
    )
    (net (code "129") (name "Net-(U15-DECAY)") (class "Default")
      (node (ref "U15") (pin "19") (pinfunction "DECAY_19") (pintype "input"))
      (node (ref "U3") (pin "5") (pinfunction "QF_5") (pintype "output"))
    )
    (net (code "130") (name "Net-(U15-ENBL)") (class "Default")
      (node (ref "U15") (pin "21") (pinfunction "ENBL_21") (pintype "input"))
      (node (ref "U3") (pin "4") (pinfunction "QE_4") (pintype "output"))
    )
    (net (code "131") (name "Net-(U15-ISENA)") (class "Default")
      (node (ref "R6") (pin "2") (pinfunction "2_2") (pintype "passive"))
      (node (ref "U15") (pin "6") (pinfunction "ISENA_6") (pintype "output"))
    )
    (net (code "132") (name "Net-(U15-ISENB)") (class "Default")
      (node (ref "R5") (pin "2") (pinfunction "2_2") (pintype "passive"))
      (node (ref "U15") (pin "9") (pinfunction "ISENB_9") (pintype "output"))
    )
    (net (code "133") (name "Net-(U15-MODE0)") (class "Default")
      (node (ref "U15") (pin "24") (pinfunction "MODE0_24") (pintype "input"))
      (node (ref "U3") (pin "3") (pinfunction "QD_3") (pintype "output"))
    )
    (net (code "134") (name "Net-(U15-MODE1)") (class "Default")
      (node (ref "U15") (pin "25") (pinfunction "MODE1_25") (pintype "input"))
      (node (ref "U3") (pin "2") (pinfunction "QC_2") (pintype "output"))
    )
    (net (code "135") (name "Net-(U15-MODE2)") (class "Default")
      (node (ref "U15") (pin "26") (pinfunction "MODE2_26") (pintype "input"))
      (node (ref "U3") (pin "1") (pinfunction "QB_1") (pintype "output"))
    )
    (net (code "136") (name "Net-(U15-RESET)") (class "Default")
      (node (ref "U15") (pin "16") (pinfunction "RESET_16") (pintype "input"))
      (node (ref "U3") (pin "7") (pinfunction "QH_7") (pintype "output"))
    )
    (net (code "137") (name "Net-(U15-SLEEP)") (class "Default")
      (node (ref "U15") (pin "17") (pinfunction "SLEEP_17") (pintype "input"))
      (node (ref "U3") (pin "6") (pinfunction "QG_6") (pintype "output"))
    )
    (net (code "138") (name "Net-(U15-VCP)") (class "Default")
      (node (ref "C6") (pin "2") (pinfunction "2_2") (pintype "passive"))
      (node (ref "U15") (pin "3") (pinfunction "VCP_3") (pintype "bidirectional"))
    )
    (net (code "139") (name "Net-(U16-AOUT1)") (class "Default")
      (node (ref "U16") (pin "5") (pinfunction "AOUT1_5") (pintype "output"))
      (node (ref "X17") (pin "4") (pinfunction "S_4") (pintype "passive"))
    )
    (net (code "140") (name "Net-(U16-AOUT2)") (class "Default")
      (node (ref "U16") (pin "7") (pinfunction "AOUT2_7") (pintype "output"))
      (node (ref "X17") (pin "3") (pinfunction "S_3") (pintype "passive"))
    )
    (net (code "141") (name "Net-(U16-BOUT1)") (class "Default")
      (node (ref "U16") (pin "10") (pinfunction "BOUT1_10") (pintype "output"))
      (node (ref "X17") (pin "2") (pinfunction "S_2") (pintype "passive"))
    )
    (net (code "142") (name "Net-(U16-BOUT2)") (class "Default")
      (node (ref "U16") (pin "8") (pinfunction "BOUT2_8") (pintype "output"))
      (node (ref "X17") (pin "1") (pinfunction "S_1") (pintype "passive"))
    )
    (net (code "143") (name "Net-(U16-CP1)") (class "Default")
      (node (ref "C7") (pin "2") (pinfunction "2_2") (pintype "passive"))
      (node (ref "U16") (pin "1") (pinfunction "CP1_1") (pintype "bidirectional"))
    )
    (net (code "144") (name "Net-(U16-CP2)") (class "Default")
      (node (ref "C7") (pin "1") (pinfunction "1_1") (pintype "passive"))
      (node (ref "U16") (pin "2") (pinfunction "CP2_2") (pintype "bidirectional"))
    )
    (net (code "145") (name "Net-(U16-DECAY)") (class "Default")
      (node (ref "U16") (pin "19") (pinfunction "DECAY_19") (pintype "input"))
      (node (ref "U4") (pin "5") (pinfunction "QF_5") (pintype "output"))
    )
    (net (code "146") (name "Net-(U16-ENBL)") (class "Default")
      (node (ref "U16") (pin "21") (pinfunction "ENBL_21") (pintype "input"))
      (node (ref "U4") (pin "4") (pinfunction "QE_4") (pintype "output"))
    )
    (net (code "147") (name "Net-(U16-ISENA)") (class "Default")
      (node (ref "R8") (pin "2") (pinfunction "2_2") (pintype "passive"))
      (node (ref "U16") (pin "6") (pinfunction "ISENA_6") (pintype "output"))
    )
    (net (code "148") (name "Net-(U16-ISENB)") (class "Default")
      (node (ref "R7") (pin "2") (pinfunction "2_2") (pintype "passive"))
      (node (ref "U16") (pin "9") (pinfunction "ISENB_9") (pintype "output"))
    )
    (net (code "149") (name "Net-(U16-MODE0)") (class "Default")
      (node (ref "U16") (pin "24") (pinfunction "MODE0_24") (pintype "input"))
      (node (ref "U4") (pin "3") (pinfunction "QD_3") (pintype "output"))
    )
    (net (code "150") (name "Net-(U16-MODE1)") (class "Default")
      (node (ref "U16") (pin "25") (pinfunction "MODE1_25") (pintype "input"))
      (node (ref "U4") (pin "2") (pinfunction "QC_2") (pintype "output"))
    )
    (net (code "151") (name "Net-(U16-MODE2)") (class "Default")
      (node (ref "U16") (pin "26") (pinfunction "MODE2_26") (pintype "input"))
      (node (ref "U4") (pin "1") (pinfunction "QB_1") (pintype "output"))
    )
    (net (code "152") (name "Net-(U16-RESET)") (class "Default")
      (node (ref "U16") (pin "16") (pinfunction "RESET_16") (pintype "input"))
      (node (ref "U4") (pin "7") (pinfunction "QH_7") (pintype "output"))
    )
    (net (code "153") (name "Net-(U16-SLEEP)") (class "Default")
      (node (ref "U16") (pin "17") (pinfunction "SLEEP_17") (pintype "input"))
      (node (ref "U4") (pin "6") (pinfunction "QG_6") (pintype "output"))
    )
    (net (code "154") (name "Net-(U16-VCP)") (class "Default")
      (node (ref "C8") (pin "2") (pinfunction "2_2") (pintype "passive"))
      (node (ref "U16") (pin "3") (pinfunction "VCP_3") (pintype "bidirectional"))
    )
    (net (code "155") (name "Net-(U17-AOUT1)") (class "Default")
      (node (ref "U17") (pin "5") (pinfunction "AOUT1_5") (pintype "output"))
      (node (ref "X18") (pin "4") (pinfunction "S_4") (pintype "passive"))
    )
    (net (code "156") (name "Net-(U17-AOUT2)") (class "Default")
      (node (ref "U17") (pin "7") (pinfunction "AOUT2_7") (pintype "output"))
      (node (ref "X18") (pin "3") (pinfunction "S_3") (pintype "passive"))
    )
    (net (code "157") (name "Net-(U17-BOUT1)") (class "Default")
      (node (ref "U17") (pin "10") (pinfunction "BOUT1_10") (pintype "output"))
      (node (ref "X18") (pin "2") (pinfunction "S_2") (pintype "passive"))
    )
    (net (code "158") (name "Net-(U17-BOUT2)") (class "Default")
      (node (ref "U17") (pin "8") (pinfunction "BOUT2_8") (pintype "output"))
      (node (ref "X18") (pin "1") (pinfunction "S_1") (pintype "passive"))
    )
    (net (code "159") (name "Net-(U17-CP1)") (class "Default")
      (node (ref "C9") (pin "2") (pinfunction "2_2") (pintype "passive"))
      (node (ref "U17") (pin "1") (pinfunction "CP1_1") (pintype "bidirectional"))
    )
    (net (code "160") (name "Net-(U17-CP2)") (class "Default")
      (node (ref "C9") (pin "1") (pinfunction "1_1") (pintype "passive"))
      (node (ref "U17") (pin "2") (pinfunction "CP2_2") (pintype "bidirectional"))
    )
    (net (code "161") (name "Net-(U17-DECAY)") (class "Default")
      (node (ref "U17") (pin "19") (pinfunction "DECAY_19") (pintype "input"))
      (node (ref "U5") (pin "5") (pinfunction "QF_5") (pintype "output"))
    )
    (net (code "162") (name "Net-(U17-ENBL)") (class "Default")
      (node (ref "U17") (pin "21") (pinfunction "ENBL_21") (pintype "input"))
      (node (ref "U5") (pin "4") (pinfunction "QE_4") (pintype "output"))
    )
    (net (code "163") (name "Net-(U17-ISENA)") (class "Default")
      (node (ref "R10") (pin "2") (pinfunction "2_2") (pintype "passive"))
      (node (ref "U17") (pin "6") (pinfunction "ISENA_6") (pintype "output"))
    )
    (net (code "164") (name "Net-(U17-ISENB)") (class "Default")
      (node (ref "R9") (pin "2") (pinfunction "2_2") (pintype "passive"))
      (node (ref "U17") (pin "9") (pinfunction "ISENB_9") (pintype "output"))
    )
    (net (code "165") (name "Net-(U17-MODE0)") (class "Default")
      (node (ref "U17") (pin "24") (pinfunction "MODE0_24") (pintype "input"))
      (node (ref "U5") (pin "3") (pinfunction "QD_3") (pintype "output"))
    )
    (net (code "166") (name "Net-(U17-MODE1)") (class "Default")
      (node (ref "U17") (pin "25") (pinfunction "MODE1_25") (pintype "input"))
      (node (ref "U5") (pin "2") (pinfunction "QC_2") (pintype "output"))
    )
    (net (code "167") (name "Net-(U17-MODE2)") (class "Default")
      (node (ref "U17") (pin "26") (pinfunction "MODE2_26") (pintype "input"))
      (node (ref "U5") (pin "1") (pinfunction "QB_1") (pintype "output"))
    )
    (net (code "168") (name "Net-(U17-RESET)") (class "Default")
      (node (ref "U17") (pin "16") (pinfunction "RESET_16") (pintype "input"))
      (node (ref "U5") (pin "7") (pinfunction "QH_7") (pintype "output"))
    )
    (net (code "169") (name "Net-(U17-SLEEP)") (class "Default")
      (node (ref "U17") (pin "17") (pinfunction "SLEEP_17") (pintype "input"))
      (node (ref "U5") (pin "6") (pinfunction "QG_6") (pintype "output"))
    )
    (net (code "170") (name "Net-(U17-VCP)") (class "Default")
      (node (ref "C10") (pin "2") (pinfunction "2_2") (pintype "passive"))
      (node (ref "U17") (pin "3") (pinfunction "VCP_3") (pintype "bidirectional"))
    )
    (net (code "171") (name "Net-(U18-A0)") (class "Default")
      (node (ref "R24") (pin "1") (pinfunction "1_1") (pintype "passive"))
      (node (ref "S2") (pin "3") (pinfunction "3_3") (pintype "passive"))
      (node (ref "U18") (pin "1") (pinfunction "A0_1") (pintype "input"))
    )
    (net (code "172") (name "Net-(U18-A1)") (class "Default")
      (node (ref "R23") (pin "1") (pinfunction "1_1") (pintype "passive"))
      (node (ref "S2") (pin "4") (pinfunction "4_4") (pintype "passive"))
      (node (ref "U18") (pin "2") (pinfunction "A1_2") (pintype "input"))
    )
    (net (code "173") (name "Net-(U18-A2)") (class "Default")
      (node (ref "R22") (pin "1") (pinfunction "1_1") (pintype "passive"))
      (node (ref "U18") (pin "3") (pinfunction "A2_3") (pintype "input"))
    )
    (net (code "174") (name "Net-(X3B-1)") (class "Default")
      (node (ref "C59") (pin "1") (pinfunction "1_1") (pintype "passive"))
      (node (ref "D1") (pin "A") (pinfunction "A_A") (pintype "passive"))
      (node (ref "LED3") (pin "C") (pinfunction "C_C") (pintype "passive"))
      (node (ref "Q3") (pin "5") (pinfunction "D_5") (pintype "passive"))
      (node (ref "Q3") (pin "6") (pinfunction "D_6") (pintype "passive"))
      (node (ref "Q3") (pin "7") (pinfunction "D_7") (pintype "passive"))
      (node (ref "Q3") (pin "8") (pinfunction "D_8") (pintype "passive"))
      (node (ref "Q3") (pin "TH") (pinfunction "D_TH") (pintype "passive"))
      (node (ref "R55") (pin "1") (pinfunction "1_1") (pintype "passive"))
      (node (ref "X3") (pin "2") (pinfunction "1_2") (pintype "passive"))
    )
    (net (code "175") (name "Net-(X4B-S)") (class "Default")
      (node (ref "LED5") (pin "C") (pinfunction "C_C") (pintype "passive"))
      (node (ref "Q4") (pin "2") (pinfunction "D_2") (pintype "passive"))
      (node (ref "Q4") (pin "4") (pinfunction "D_4") (pintype "passive"))
      (node (ref "X4") (pin "2") (pinfunction "S_2") (pintype "passive"))
    )
    (net (code "176") (name "Net-(X5B-S)") (class "Default")
      (node (ref "LED6") (pin "C") (pinfunction "C_C") (pintype "passive"))
      (node (ref "Q5") (pin "2") (pinfunction "D_2") (pintype "passive"))
      (node (ref "Q5") (pin "4") (pinfunction "D_4") (pintype "passive"))
      (node (ref "X5") (pin "2") (pinfunction "S_2") (pintype "passive"))
    )
    (net (code "177") (name "Net-(X6B-S)") (class "Default")
      (node (ref "LED7") (pin "C") (pinfunction "C_C") (pintype "passive"))
      (node (ref "Q6") (pin "2") (pinfunction "D_2") (pintype "passive"))
      (node (ref "Q6") (pin "4") (pinfunction "D_4") (pintype "passive"))
      (node (ref "X6") (pin "2") (pinfunction "S_2") (pintype "passive"))
    )
    (net (code "178") (name "Net-(X7A-S)") (class "Default")
      (node (ref "C16") (pin "1") (pinfunction "1_1") (pintype "passive"))
      (node (ref "R18") (pin "1") (pinfunction "1_1") (pintype "passive"))
      (node (ref "R40") (pin "1") (pinfunction "1_1") (pintype "passive"))
      (node (ref "X7") (pin "1") (pinfunction "S_1") (pintype "passive"))
    )
    (net (code "179") (name "Net-(X8A-S)") (class "Default")
      (node (ref "C15") (pin "1") (pinfunction "1_1") (pintype "passive"))
      (node (ref "R17") (pin "1") (pinfunction "1_1") (pintype "passive"))
      (node (ref "R39") (pin "1") (pinfunction "1_1") (pintype "passive"))
      (node (ref "X8") (pin "1") (pinfunction "S_1") (pintype "passive"))
    )
    (net (code "180") (name "Net-(X9A-S)") (class "Default")
      (node (ref "C14") (pin "1") (pinfunction "1_1") (pintype "passive"))
      (node (ref "R13") (pin "1") (pinfunction "1_1") (pintype "passive"))
      (node (ref "R38") (pin "1") (pinfunction "1_1") (pintype "passive"))
      (node (ref "X9") (pin "1") (pinfunction "S_1") (pintype "passive"))
    )
    (net (code "181") (name "Net-(X20C-1)") (class "Default")
      (node (ref "C58") (pin "1") (pinfunction "1_1") (pintype "passive"))
      (node (ref "D2") (pin "A") (pinfunction "A_A") (pintype "passive"))
      (node (ref "LED2") (pin "C") (pinfunction "C_C") (pintype "passive"))
      (node (ref "Q1") (pin "5") (pinfunction "D_5") (pintype "passive"))
      (node (ref "Q1") (pin "6") (pinfunction "D_6") (pintype "passive"))
      (node (ref "Q1") (pin "7") (pinfunction "D_7") (pintype "passive"))
      (node (ref "Q1") (pin "8") (pinfunction "D_8") (pintype "passive"))
      (node (ref "Q1") (pin "TH") (pinfunction "D_TH") (pintype "passive"))
      (node (ref "R56") (pin "1") (pinfunction "1_1") (pintype "passive"))
      (node (ref "X20") (pin "3") (pinfunction "1_3") (pintype "passive"))
      (node (ref "X20") (pin "4") (pinfunction "1_4") (pintype "passive"))
    )
    (net (code "182") (name "Net-(X21B-1)") (class "Default")
      (node (ref "C57") (pin "1") (pinfunction "1_1") (pintype "passive"))
      (node (ref "D3") (pin "A") (pinfunction "A_A") (pintype "passive"))
      (node (ref "LED1") (pin "C") (pinfunction "C_C") (pintype "passive"))
      (node (ref "Q2") (pin "5") (pinfunction "D_5") (pintype "passive"))
      (node (ref "Q2") (pin "6") (pinfunction "D_6") (pintype "passive"))
      (node (ref "Q2") (pin "7") (pinfunction "D_7") (pintype "passive"))
      (node (ref "Q2") (pin "8") (pinfunction "D_8") (pintype "passive"))
      (node (ref "Q2") (pin "TH") (pinfunction "D_TH") (pintype "passive"))
      (node (ref "R57") (pin "1") (pinfunction "1_1") (pintype "passive"))
      (node (ref "X21") (pin "2") (pinfunction "1_2") (pintype "passive"))
    )
    (net (code "183") (name "unconnected-(P8-Pad3)") (class "Default")
      (node (ref "P8") (pin "3") (pinfunction "3_3") (pintype "passive"))
    )
    (net (code "184") (name "unconnected-(P8-Pad4)") (class "Default")
      (node (ref "P8") (pin "4") (pinfunction "4_4") (pintype "passive"))
    )
    (net (code "185") (name "unconnected-(P8-Pad5)") (class "Default")
      (node (ref "P8") (pin "5") (pinfunction "5_5") (pintype "passive"))
    )
    (net (code "186") (name "unconnected-(P8-Pad6)") (class "Default")
      (node (ref "P8") (pin "6") (pinfunction "6_6") (pintype "passive"))
    )
    (net (code "187") (name "unconnected-(P8-Pad7)") (class "Default")
      (node (ref "P8") (pin "7") (pinfunction "7_7") (pintype "passive"))
    )
    (net (code "188") (name "unconnected-(P8-Pad20)") (class "Default")
      (node (ref "P8") (pin "20") (pinfunction "20_20") (pintype "passive"))
    )
    (net (code "189") (name "unconnected-(P8-Pad21)") (class "Default")
      (node (ref "P8") (pin "21") (pinfunction "21_21") (pintype "passive"))
    )
    (net (code "190") (name "unconnected-(P8-Pad22)") (class "Default")
      (node (ref "P8") (pin "22") (pinfunction "22_22") (pintype "passive"))
    )
    (net (code "191") (name "unconnected-(P8-Pad23)") (class "Default")
      (node (ref "P8") (pin "23") (pinfunction "23_23") (pintype "passive"))
    )
    (net (code "192") (name "unconnected-(P8-Pad24)") (class "Default")
      (node (ref "P8") (pin "24") (pinfunction "24_24") (pintype "passive"))
    )
    (net (code "193") (name "unconnected-(P8-Pad25)") (class "Default")
      (node (ref "P8") (pin "25") (pinfunction "25_25") (pintype "passive"))
    )
    (net (code "194") (name "unconnected-(P8-Pad27)") (class "Default")
      (node (ref "P8") (pin "27") (pinfunction "27_27") (pintype "passive"))
    )
    (net (code "195") (name "unconnected-(P8-Pad28)") (class "Default")
      (node (ref "P8") (pin "28") (pinfunction "28_28") (pintype "passive"))
    )
    (net (code "196") (name "unconnected-(P8-Pad29)") (class "Default")
      (node (ref "P8") (pin "29") (pinfunction "29_29") (pintype "passive"))
    )
    (net (code "197") (name "unconnected-(P8-Pad30)") (class "Default")
      (node (ref "P8") (pin "30") (pinfunction "30_30") (pintype "passive"))
    )
    (net (code "198") (name "unconnected-(P8-Pad31)") (class "Default")
      (node (ref "P8") (pin "31") (pinfunction "31_31") (pintype "passive"))
    )
    (net (code "199") (name "unconnected-(P8-Pad32)") (class "Default")
      (node (ref "P8") (pin "32") (pinfunction "32_32") (pintype "passive"))
    )
    (net (code "200") (name "unconnected-(P8-Pad33)") (class "Default")
      (node (ref "P8") (pin "33") (pinfunction "33_33") (pintype "passive"))
    )
    (net (code "201") (name "unconnected-(P8-Pad34)") (class "Default")
      (node (ref "P8") (pin "34") (pinfunction "34_34") (pintype "passive"))
    )
    (net (code "202") (name "unconnected-(P8-Pad35)") (class "Default")
      (node (ref "P8") (pin "35") (pinfunction "35_35") (pintype "passive"))
    )
    (net (code "203") (name "unconnected-(P8-Pad36)") (class "Default")
      (node (ref "P8") (pin "36") (pinfunction "36_36") (pintype "passive"))
    )
    (net (code "204") (name "unconnected-(P8-Pad37)") (class "Default")
      (node (ref "P8") (pin "37") (pinfunction "37_37") (pintype "passive"))
    )
    (net (code "205") (name "unconnected-(P8-Pad38)") (class "Default")
      (node (ref "P8") (pin "38") (pinfunction "38_38") (pintype "passive"))
    )
    (net (code "206") (name "unconnected-(P8-Pad39)") (class "Default")
      (node (ref "P8") (pin "39") (pinfunction "39_39") (pintype "passive"))
    )
    (net (code "207") (name "unconnected-(P8-Pad40)") (class "Default")
      (node (ref "P8") (pin "40") (pinfunction "40_40") (pintype "passive"))
    )
    (net (code "208") (name "unconnected-(P8-Pad41)") (class "Default")
      (node (ref "P8") (pin "41") (pinfunction "41_41") (pintype "passive"))
    )
    (net (code "209") (name "unconnected-(P8-Pad42)") (class "Default")
      (node (ref "P8") (pin "42") (pinfunction "42_42") (pintype "passive"))
    )
    (net (code "210") (name "unconnected-(P8-Pad43)") (class "Default")
      (node (ref "P8") (pin "43") (pinfunction "43_43") (pintype "passive"))
    )
    (net (code "211") (name "unconnected-(P8-Pad44)") (class "Default")
      (node (ref "P8") (pin "44") (pinfunction "44_44") (pintype "passive"))
    )
    (net (code "212") (name "unconnected-(P8-Pad45)") (class "Default")
      (node (ref "P8") (pin "45") (pinfunction "45_45") (pintype "passive"))
    )
    (net (code "213") (name "unconnected-(P8-Pad46)") (class "Default")
      (node (ref "P8") (pin "46") (pinfunction "46_46") (pintype "passive"))
    )
    (net (code "214") (name "unconnected-(P9-Pad9)") (class "Default")
      (node (ref "P9") (pin "9") (pinfunction "9_9") (pintype "passive"))
    )
    (net (code "215") (name "unconnected-(P9-Pad10)") (class "Default")
      (node (ref "P9") (pin "10") (pinfunction "10_10") (pintype "passive"))
    )
    (net (code "216") (name "unconnected-(P9-Pad14)") (class "Default")
      (node (ref "P9") (pin "14") (pinfunction "14_14") (pintype "passive"))
    )
    (net (code "217") (name "unconnected-(P9-Pad15)") (class "Default")
      (node (ref "P9") (pin "15") (pinfunction "15_15") (pintype "passive"))
    )
    (net (code "218") (name "unconnected-(P9-Pad17)") (class "Default")
      (node (ref "P9") (pin "17") (pinfunction "17_17") (pintype "passive"))
    )
    (net (code "219") (name "unconnected-(P9-Pad21)") (class "Default")
      (node (ref "P9") (pin "21") (pinfunction "21_21") (pintype "passive"))
    )
    (net (code "220") (name "unconnected-(P9-Pad26)") (class "Default")
      (node (ref "P9") (pin "26") (pinfunction "26_26") (pintype "passive"))
    )
    (net (code "221") (name "unconnected-(P9-Pad27)") (class "Default")
      (node (ref "P9") (pin "27") (pinfunction "27_27") (pintype "passive"))
    )
    (net (code "222") (name "unconnected-(P9-Pad37)") (class "Default")
      (node (ref "P9") (pin "37") (pinfunction "37_37") (pintype "passive"))
    )
    (net (code "223") (name "unconnected-(P9-Pad38)") (class "Default")
      (node (ref "P9") (pin "38") (pinfunction "38_38") (pintype "passive"))
    )
    (net (code "224") (name "unconnected-(P9-Pad39)") (class "Default")
      (node (ref "P9") (pin "39") (pinfunction "39_39") (pintype "passive"))
    )
    (net (code "225") (name "unconnected-(P9-Pad40)") (class "Default")
      (node (ref "P9") (pin "40") (pinfunction "40_40") (pintype "passive"))
    )
    (net (code "226") (name "unconnected-(P9-Pad41)") (class "Default")
      (node (ref "P9") (pin "41") (pinfunction "41_41") (pintype "passive"))
    )
    (net (code "227") (name "unconnected-(U1-QA-Pad15)") (class "Default")
      (node (ref "U1") (pin "15") (pinfunction "QA_15") (pintype "output"))
    )
    (net (code "228") (name "unconnected-(U2-QA-Pad15)") (class "Default")
      (node (ref "U2") (pin "15") (pinfunction "QA_15") (pintype "output"))
    )
    (net (code "229") (name "unconnected-(U3-QA-Pad15)") (class "Default")
      (node (ref "U3") (pin "15") (pinfunction "QA_15") (pintype "output"))
    )
    (net (code "230") (name "unconnected-(U4-QA-Pad15)") (class "Default")
      (node (ref "U4") (pin "15") (pinfunction "QA_15") (pintype "output"))
    )
    (net (code "231") (name "unconnected-(U5-QA-Pad15)") (class "Default")
      (node (ref "U5") (pin "15") (pinfunction "QA_15") (pintype "output"))
    )
    (net (code "232") (name "unconnected-(U5-QH_2-Pad9)") (class "Default")
      (node (ref "U5") (pin "9") (pinfunction "QH_2_9") (pintype "output"))
    )
    (net (code "233") (name "unconnected-(U6-EN-Pad9)") (class "Default")
      (node (ref "U6") (pin "9") (pinfunction "EN_9") (pintype "input"))
    )
    (net (code "234") (name "unconnected-(U10-EN-Pad9)") (class "Default")
      (node (ref "U10") (pin "9") (pinfunction "EN_9") (pintype "input"))
    )
    (net (code "235") (name "unconnected-(U11-EXTCLK-Pad25)") (class "Default")
      (node (ref "U11") (pin "25") (pinfunction "EXTCLK_25") (pintype "input"))
    )
    (net (code "236") (name "unconnected-(U11-LED0-Pad6)") (class "Default")
      (node (ref "U11") (pin "6") (pinfunction "LED0_6") (pintype "output"))
    )
    (net (code "237") (name "unconnected-(U11-LED1-Pad7)") (class "Default")
      (node (ref "U11") (pin "7") (pinfunction "LED1_7") (pintype "output"))
    )
    (net (code "238") (name "unconnected-(U11-LED2-Pad8)") (class "Default")
      (node (ref "U11") (pin "8") (pinfunction "LED2_8") (pintype "output"))
    )
    (net (code "239") (name "unconnected-(U11-LED6-Pad12)") (class "Default")
      (node (ref "U11") (pin "12") (pinfunction "LED6_12") (pintype "output"))
    )
    (net (code "240") (name "unconnected-(U11-LED7-Pad13)") (class "Default")
      (node (ref "U11") (pin "13") (pinfunction "LED7_13") (pintype "output"))
    )
    (net (code "241") (name "unconnected-(U11-LED11-Pad18)") (class "Default")
      (node (ref "U11") (pin "18") (pinfunction "LED11_18") (pintype "output"))
    )
    (net (code "242") (name "unconnected-(U11-LED12-Pad19)") (class "Default")
      (node (ref "U11") (pin "19") (pinfunction "LED12_19") (pintype "output"))
    )
    (net (code "243") (name "unconnected-(U11-LED13-Pad20)") (class "Default")
      (node (ref "U11") (pin "20") (pinfunction "LED13_20") (pintype "output"))
    )
    (net (code "244") (name "unconnected-(U11-LED14-Pad21)") (class "Default")
      (node (ref "U11") (pin "21") (pinfunction "LED14_21") (pintype "output"))
    )
    (net (code "245") (name "unconnected-(U11-LED15-Pad22)") (class "Default")
      (node (ref "U11") (pin "22") (pinfunction "LED15_22") (pintype "output"))
    )
    (net (code "246") (name "unconnected-(U12-P$11-VOUTH-Pad11)") (class "Default")
      (node (ref "U12") (pin "11") (pinfunction "P$11-VOUTH_11") (pintype "bidirectional"))
    )
    (net (code "247") (name "unconnected-(U12-P$12-VOUTG-Pad12)") (class "Default")
      (node (ref "U12") (pin "12") (pinfunction "P$12-VOUTG_12") (pintype "bidirectional"))
    )
    (net (code "248") (name "unconnected-(U12-P$13-VOUTF-Pad13)") (class "Default")
      (node (ref "U12") (pin "13") (pinfunction "P$13-VOUTF_13") (pintype "bidirectional"))
    )
    (net (code "249") (name "unconnected-(U13-HOME-Pad27)") (class "Default")
      (node (ref "U13") (pin "27") (pinfunction "HOME_27") (pintype "output"))
    )
    (net (code "250") (name "unconnected-(U13-V3P3OUT-Pad15)") (class "Default")
      (node (ref "U13") (pin "15") (pinfunction "V3P3OUT_15") (pintype "output"))
    )
    (net (code "251") (name "unconnected-(U14-HOME-Pad27)") (class "Default")
      (node (ref "U14") (pin "27") (pinfunction "HOME_27") (pintype "output"))
    )
    (net (code "252") (name "unconnected-(U14-V3P3OUT-Pad15)") (class "Default")
      (node (ref "U14") (pin "15") (pinfunction "V3P3OUT_15") (pintype "output"))
    )
    (net (code "253") (name "unconnected-(U15-HOME-Pad27)") (class "Default")
      (node (ref "U15") (pin "27") (pinfunction "HOME_27") (pintype "output"))
    )
    (net (code "254") (name "unconnected-(U15-V3P3OUT-Pad15)") (class "Default")
      (node (ref "U15") (pin "15") (pinfunction "V3P3OUT_15") (pintype "output"))
    )
    (net (code "255") (name "unconnected-(U16-HOME-Pad27)") (class "Default")
      (node (ref "U16") (pin "27") (pinfunction "HOME_27") (pintype "output"))
    )
    (net (code "256") (name "unconnected-(U16-V3P3OUT-Pad15)") (class "Default")
      (node (ref "U16") (pin "15") (pinfunction "V3P3OUT_15") (pintype "output"))
    )
    (net (code "257") (name "unconnected-(U17-HOME-Pad27)") (class "Default")
      (node (ref "U17") (pin "27") (pinfunction "HOME_27") (pintype "output"))
    )
    (net (code "258") (name "unconnected-(U17-V3P3OUT-Pad15)") (class "Default")
      (node (ref "U17") (pin "15") (pinfunction "V3P3OUT_15") (pintype "output"))
    )
    (net (code "259") (name "unconnected-(U18-~{WC}-Pad7)") (class "Default")
      (node (ref "U18") (pin "7") (pinfunction "~{WC}_7") (pintype "no_connect"))
    )
  )
)
